# pepino4.net
KiCad netlist of a schematic drawn in EAGLE
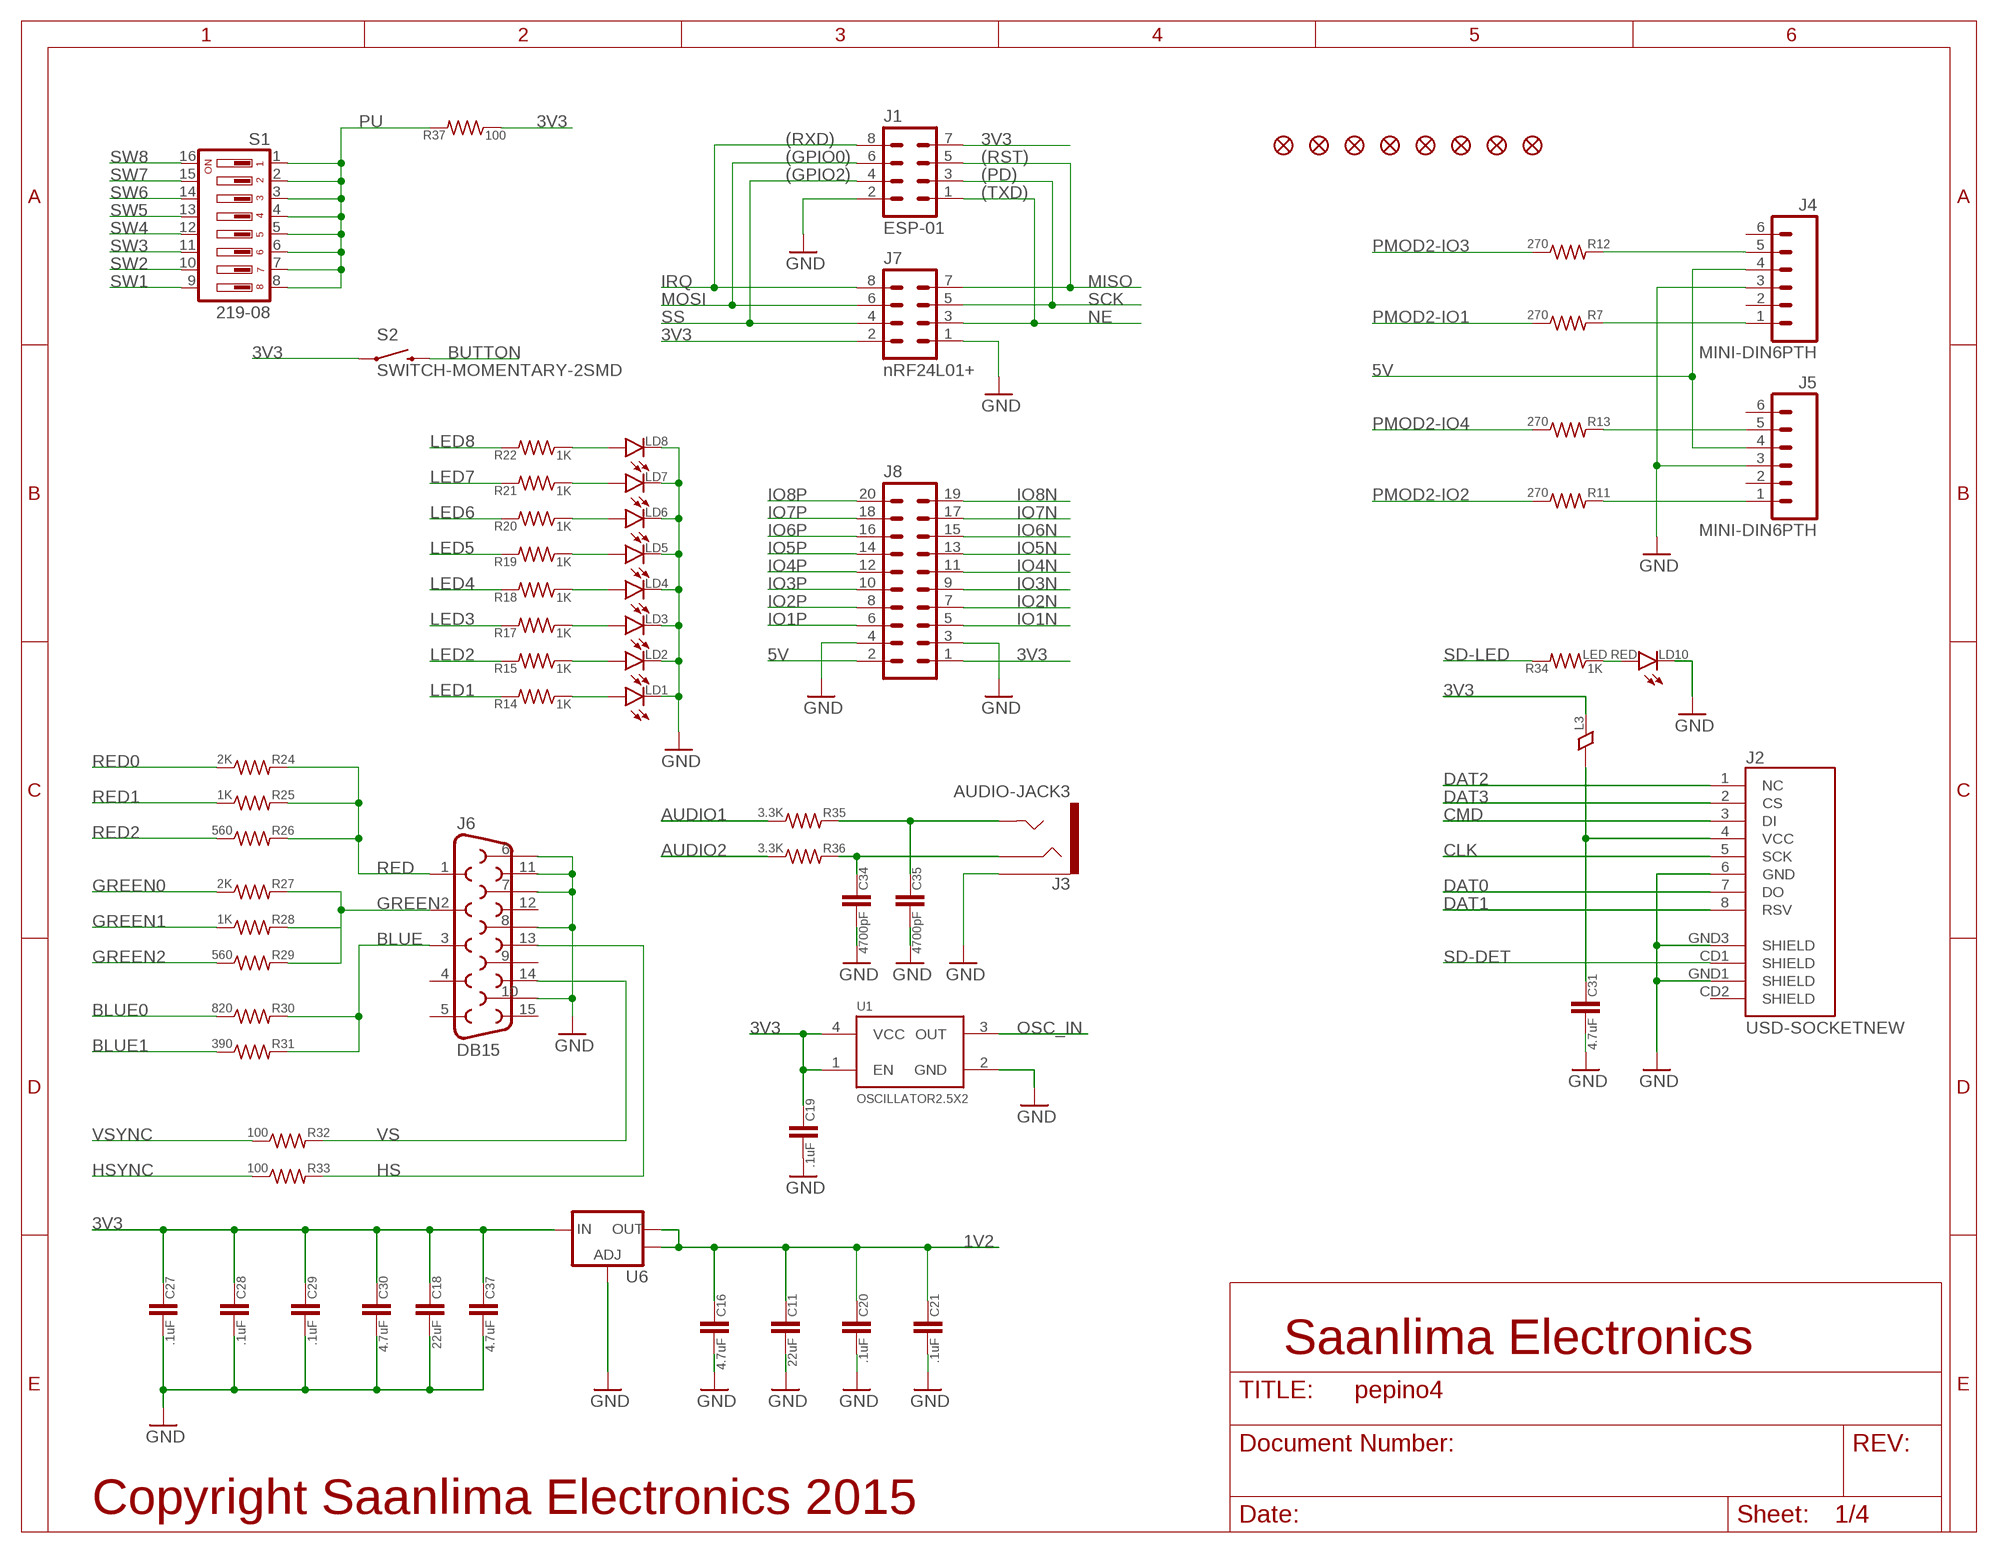
[diagram p0: schematic, sheet 1]
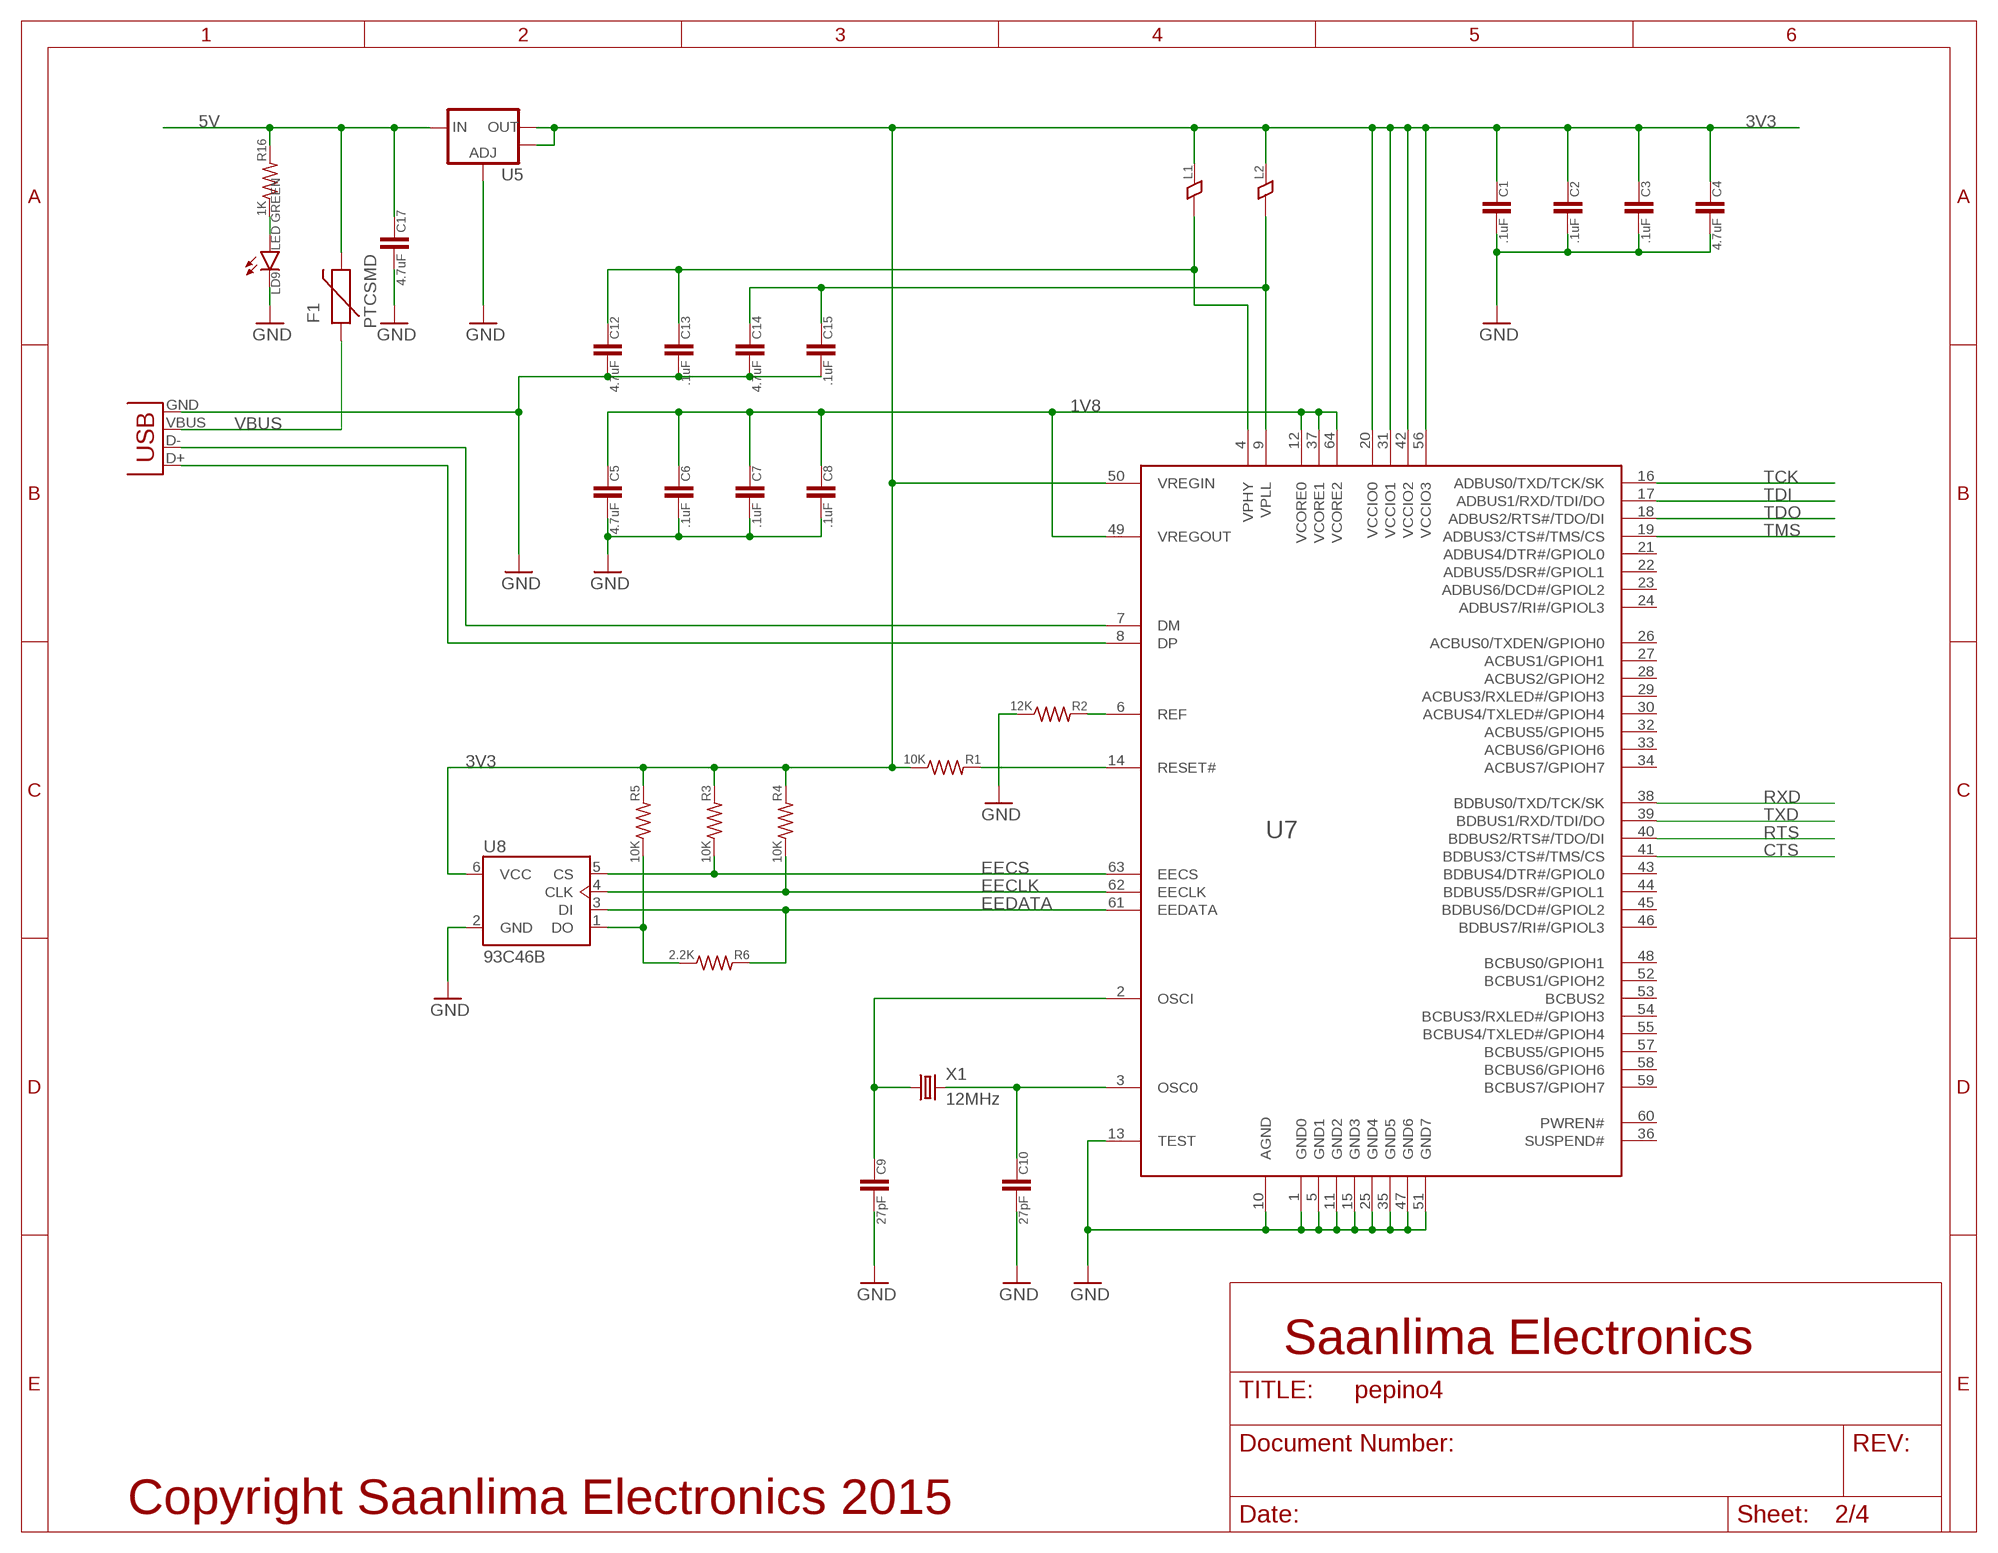
[diagram p1: schematic, sheet 2]
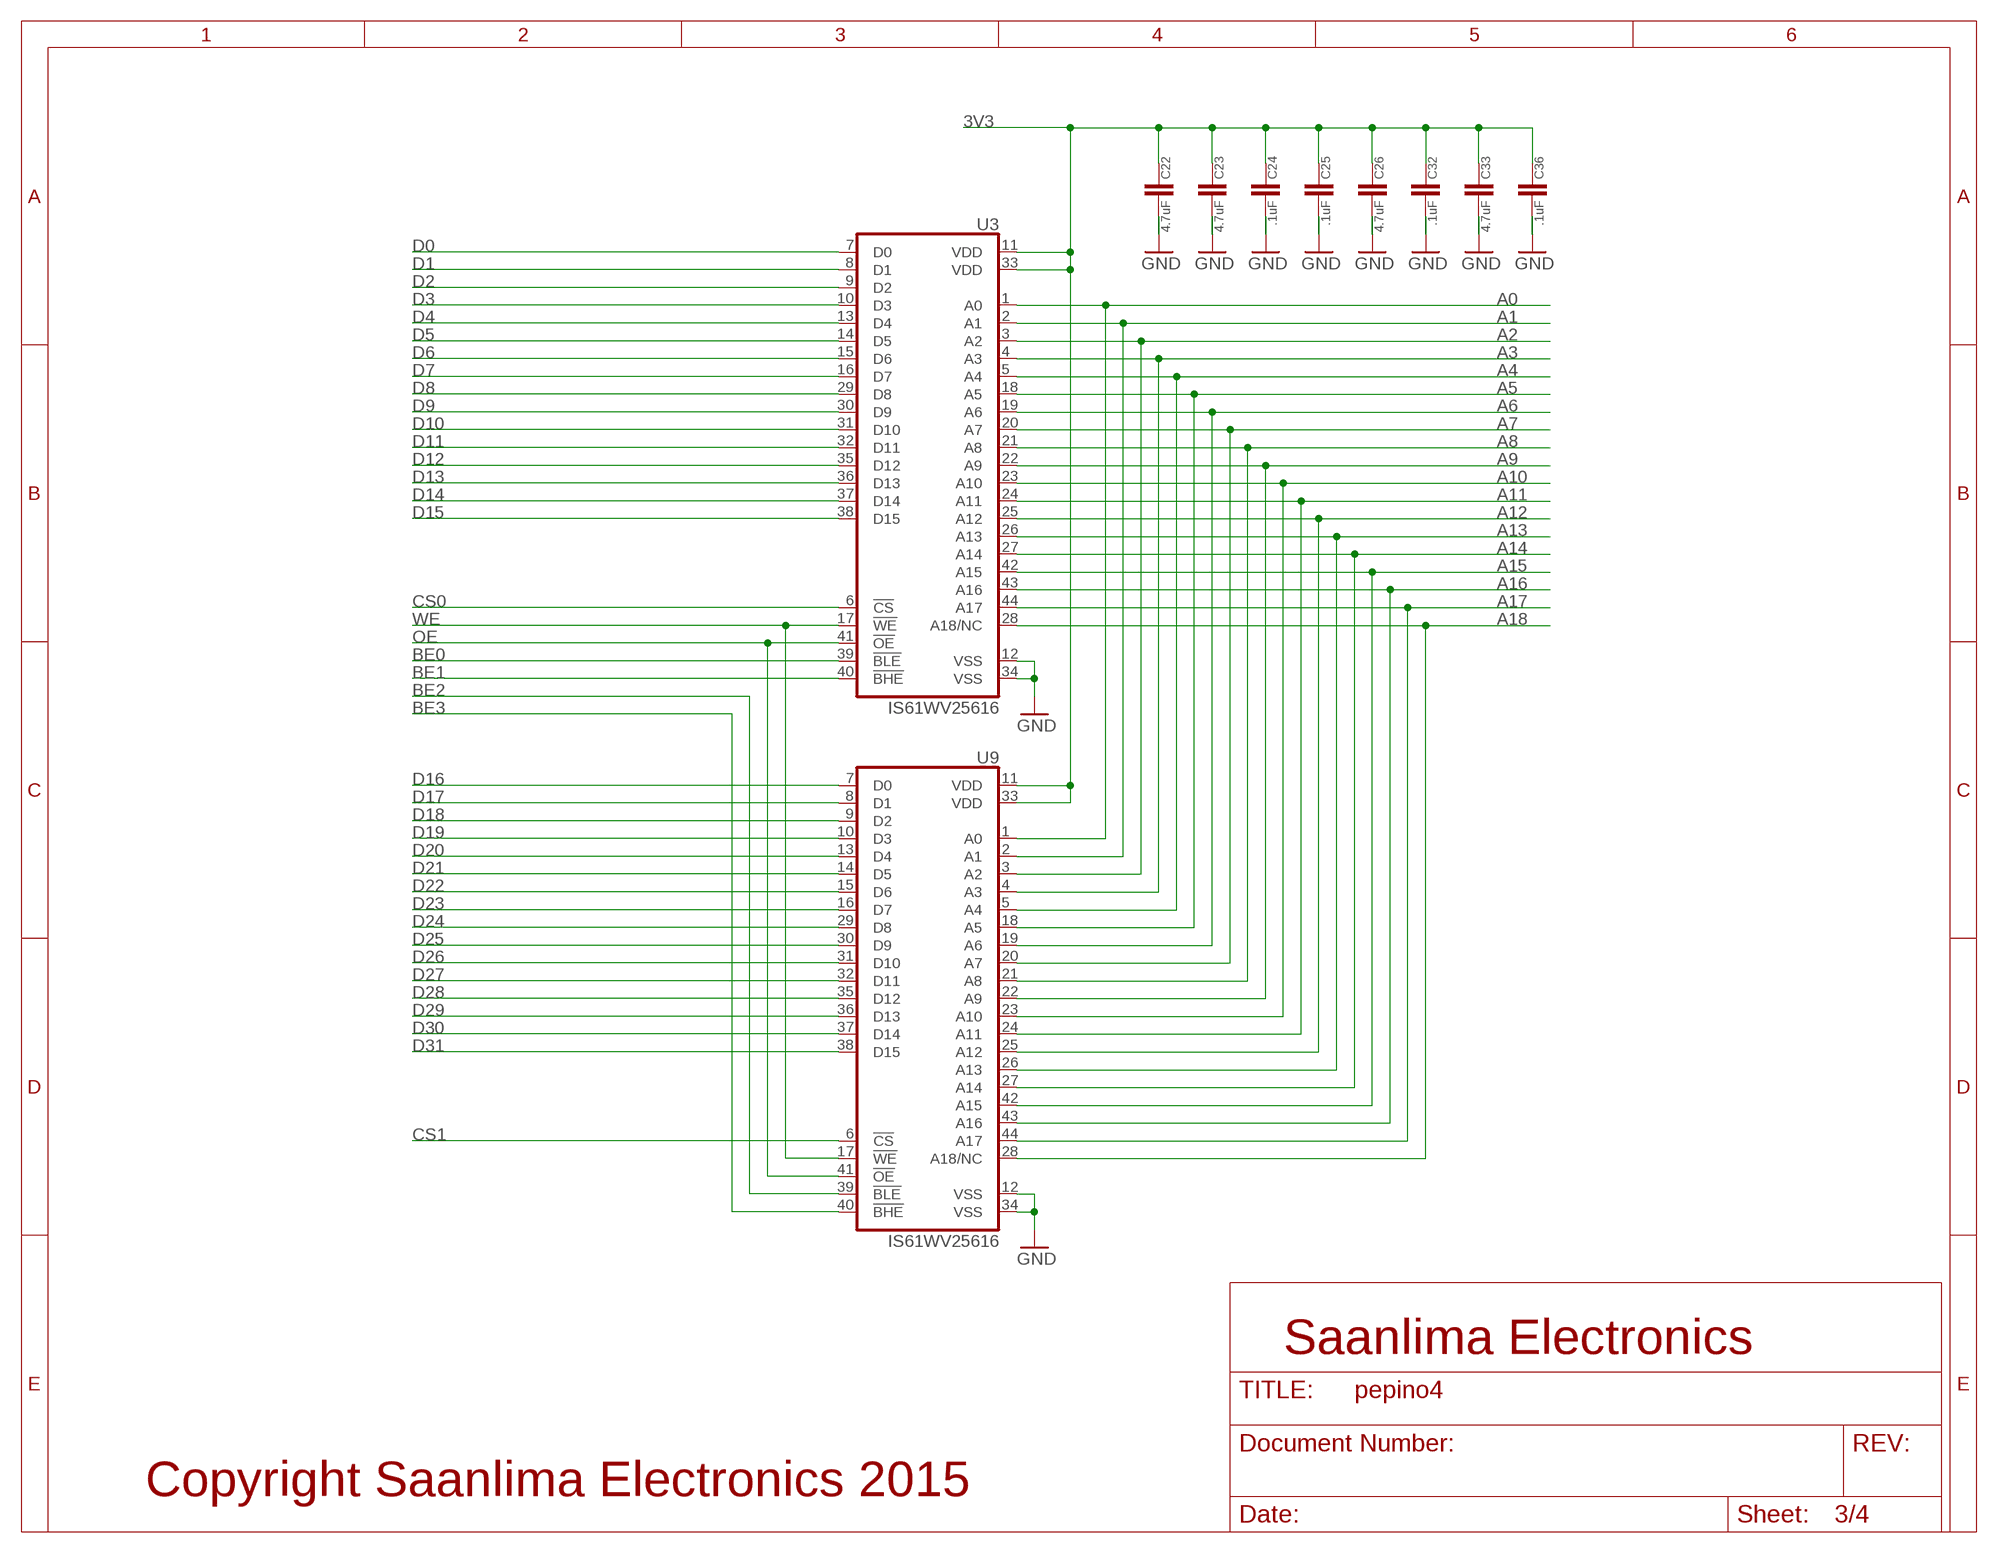
[diagram p2: schematic, sheet 3]
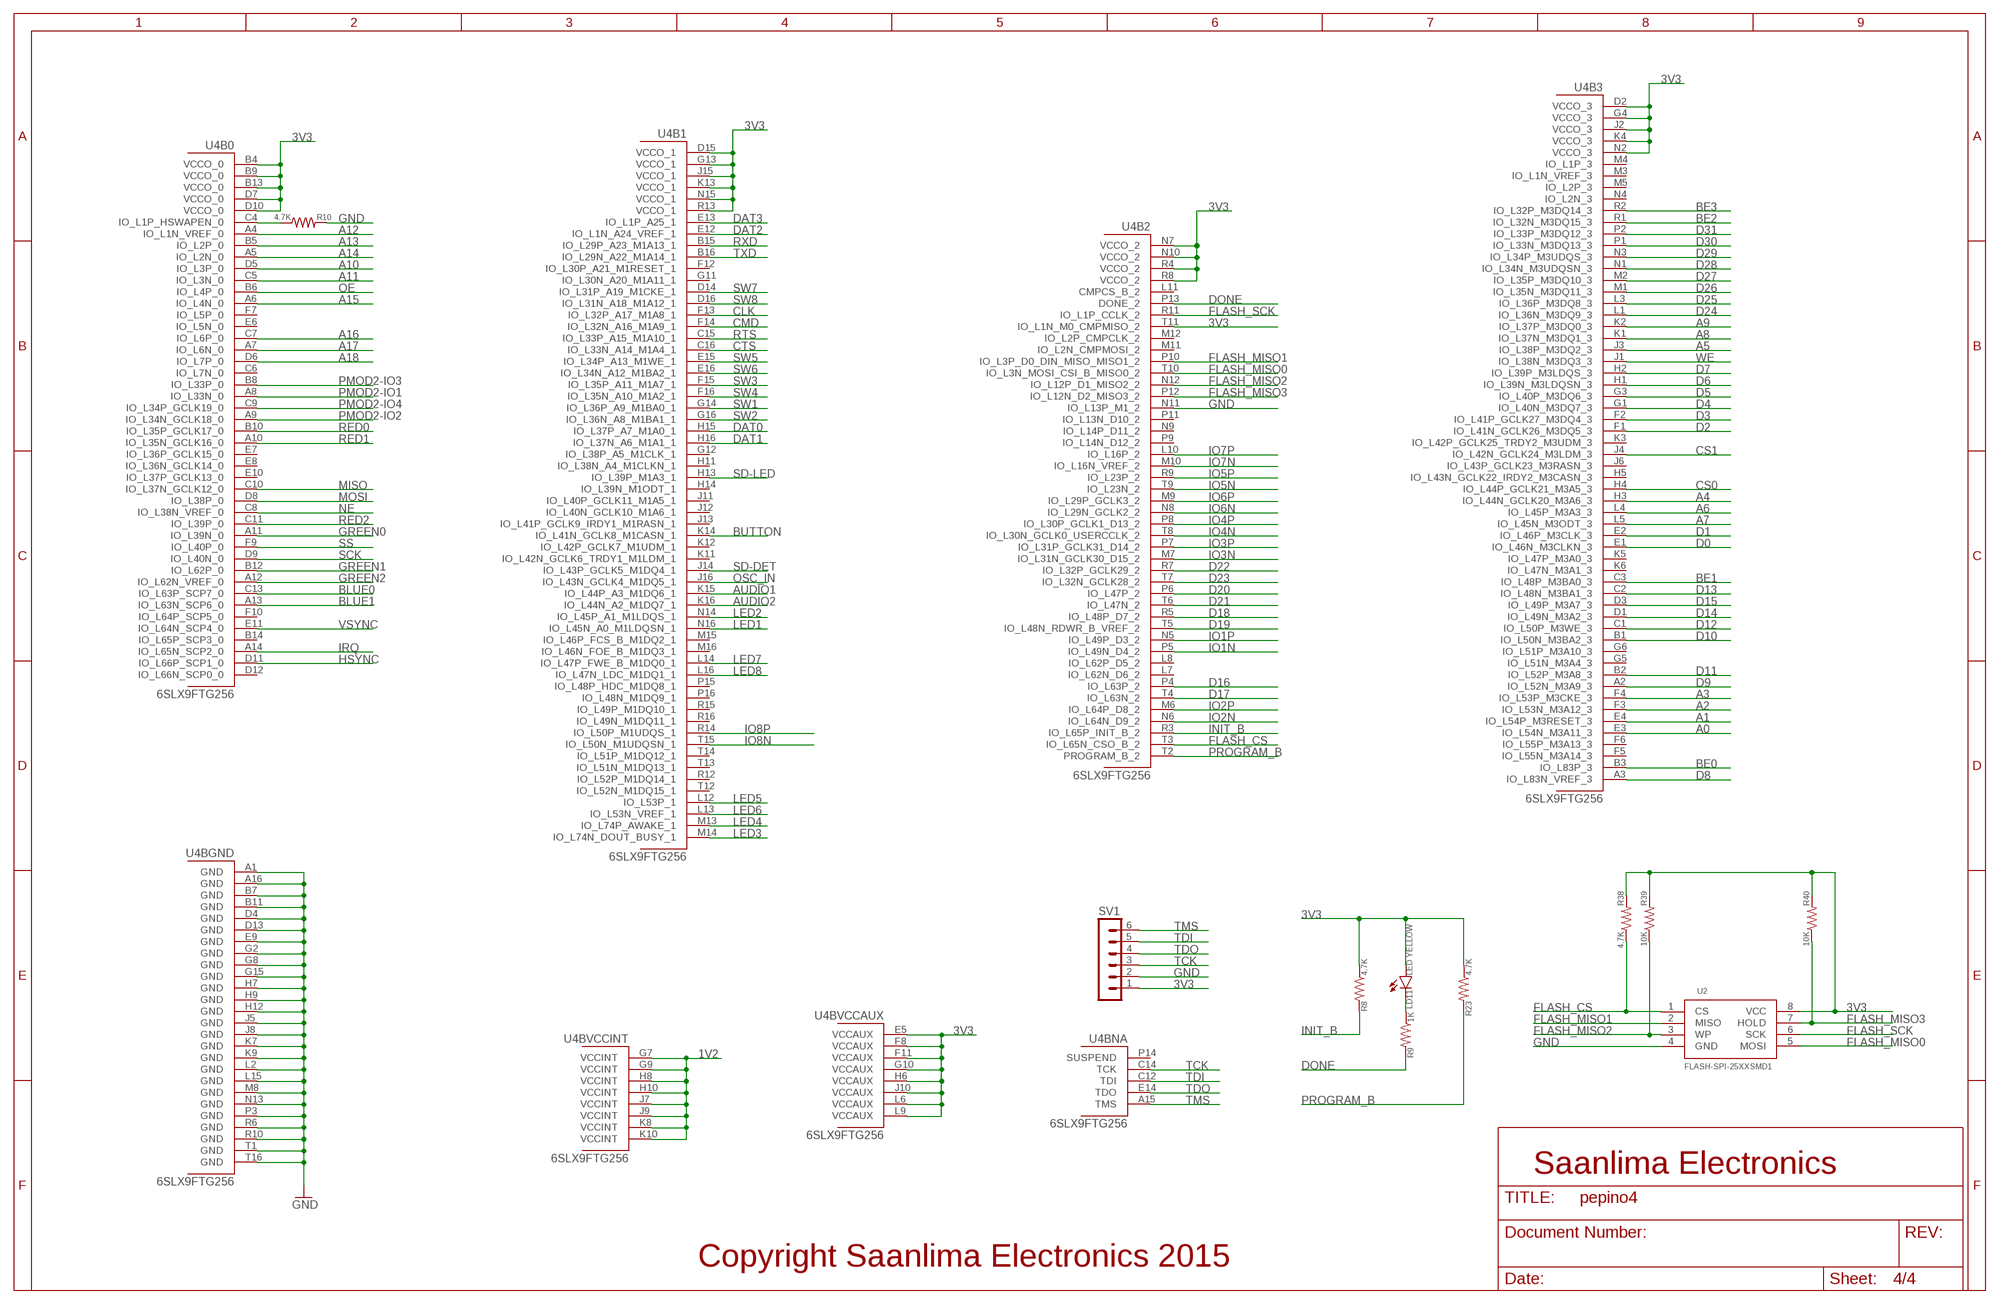
[diagram p3: schematic, sheet 4]

(export (version "E")
  (design (tool "Eeschema 10.0.6"))
  (components
    (comp (ref "C1")
      (value ".1uF")
      (footprint "eagle-import:0402")
      (libsource (lib "eagle-import") (part "saanlima_C0402"))
    )
    (comp (ref "C2")
      (value ".1uF")
      (footprint "eagle-import:0402")
      (libsource (lib "eagle-import") (part "saanlima_C0402"))
    )
    (comp (ref "C3")
      (value ".1uF")
      (footprint "eagle-import:0402")
      (libsource (lib "eagle-import") (part "saanlima_C0402"))
    )
    (comp (ref "C4")
      (value "4.7uF")
      (footprint "eagle-import:0402")
      (libsource (lib "eagle-import") (part "saanlima_C0402"))
    )
    (comp (ref "C5")
      (value "4.7uF")
      (footprint "eagle-import:0402")
      (libsource (lib "eagle-import") (part "saanlima_C0402"))
    )
    (comp (ref "C6")
      (value ".1uF")
      (footprint "eagle-import:0402")
      (libsource (lib "eagle-import") (part "saanlima_C0402"))
    )
    (comp (ref "C7")
      (value ".1uF")
      (footprint "eagle-import:0402")
      (libsource (lib "eagle-import") (part "saanlima_C0402"))
    )
    (comp (ref "C8")
      (value ".1uF")
      (footprint "eagle-import:0402")
      (libsource (lib "eagle-import") (part "saanlima_C0402"))
    )
    (comp (ref "C9")
      (value "27pF")
      (footprint "eagle-import:0402")
      (libsource (lib "eagle-import") (part "saanlima_C0402"))
    )
    (comp (ref "C10")
      (value "27pF")
      (footprint "eagle-import:0402")
      (libsource (lib "eagle-import") (part "saanlima_C0402"))
    )
    (comp (ref "C12")
      (value "4.7uF")
      (footprint "eagle-import:0402")
      (libsource (lib "eagle-import") (part "saanlima_C0402"))
    )
    (comp (ref "C13")
      (value ".1uF")
      (footprint "eagle-import:0402")
      (libsource (lib "eagle-import") (part "saanlima_C0402"))
    )
    (comp (ref "C14")
      (value "4.7uF")
      (footprint "eagle-import:0402")
      (libsource (lib "eagle-import") (part "saanlima_C0402"))
    )
    (comp (ref "C15")
      (value ".1uF")
      (footprint "eagle-import:0402")
      (libsource (lib "eagle-import") (part "saanlima_C0402"))
    )
    (comp (ref "C17")
      (value "4.7uF")
      (footprint "eagle-import:0603")
      (libsource (lib "eagle-import") (part "saanlima_C0603"))
    )
    (comp (ref "F1")
      (value "PTCSMD")
      (footprint "eagle-import:PTC-1206")
      (libsource (lib "eagle-import") (part "PTCSMD"))
    )
    (comp (ref "J9")
      (value "USBSMD")
      (footprint "eagle-import:USB-MINIB")
      (libsource (lib "eagle-import") (part "USBSMD"))
    )
    (comp (ref "L1")
      (value "FERRITE0402")
      (footprint "eagle-import:0402")
      (libsource (lib "eagle-import") (part "FERRITE0402"))
    )
    (comp (ref "L2")
      (value "FERRITE0402")
      (footprint "eagle-import:0402")
      (libsource (lib "eagle-import") (part "FERRITE0402"))
    )
    (comp (ref "LD9")
      (value "LED GREEN")
      (footprint "eagle-import:0805_POL")
      (libsource (lib "eagle-import") (part "LED0805"))
    )
    (comp (ref "R1")
      (value "10K")
      (footprint "eagle-import:0402")
      (libsource (lib "eagle-import") (part "saanlima_R0402"))
    )
    (comp (ref "R2")
      (value "12K")
      (footprint "eagle-import:0402")
      (libsource (lib "eagle-import") (part "saanlima_R0402"))
    )
    (comp (ref "R3")
      (value "10K")
      (footprint "eagle-import:0402")
      (libsource (lib "eagle-import") (part "saanlima_R0402"))
    )
    (comp (ref "R4")
      (value "10K")
      (footprint "eagle-import:0402")
      (libsource (lib "eagle-import") (part "saanlima_R0402"))
    )
    (comp (ref "R5")
      (value "10K")
      (footprint "eagle-import:0402")
      (libsource (lib "eagle-import") (part "saanlima_R0402"))
    )
    (comp (ref "R6")
      (value "2.2K")
      (footprint "eagle-import:0402")
      (libsource (lib "eagle-import") (part "saanlima_R0402"))
    )
    (comp (ref "R16")
      (value "1K")
      (footprint "eagle-import:0402")
      (libsource (lib "eagle-import") (part "saanlima_R0402"))
    )
    (comp (ref "U5")
      (value "V_REG_LM1117SOT223")
      (footprint "eagle-import:SOT223")
      (libsource (lib "eagle-import") (part "V_REG_LM1117SOT223"))
    )
    (comp (ref "U7")
      (value "DP-EAGLELIBRARY_FT2232H")
      (footprint "eagle-import:DP-EAGLELIBRARY_LQFP64")
      (libsource (lib "eagle-import") (part "DP-EAGLELIBRARY_FT2232H"))
    )
    (comp (ref "U8")
      (value "93C46B")
      (footprint "eagle-import:SOT23-6")
      (libsource (lib "eagle-import") (part "DIGITAL-EEPROM-MICROWIRE-6P_SOT23"))
    )
    (comp (ref "X1")
      (value "12MHz")
      (footprint "eagle-import:CRYSTAL3.2X2.5MM")
      (libsource (lib "eagle-import") (part "CRYSTAL3.2X2.5"))
    )
    (comp (ref "C22")
      (value "4.7uF")
      (footprint "eagle-import:0402")
      (libsource (lib "eagle-import") (part "saanlima_C0402"))
    )
    (comp (ref "C23")
      (value "4.7uF")
      (footprint "eagle-import:0402")
      (libsource (lib "eagle-import") (part "saanlima_C0402"))
    )
    (comp (ref "C24")
      (value ".1uF")
      (footprint "eagle-import:0402")
      (libsource (lib "eagle-import") (part "saanlima_C0402"))
    )
    (comp (ref "C25")
      (value ".1uF")
      (footprint "eagle-import:0402")
      (libsource (lib "eagle-import") (part "saanlima_C0402"))
    )
    (comp (ref "C26")
      (value "4.7uF")
      (footprint "eagle-import:0402")
      (libsource (lib "eagle-import") (part "saanlima_C0402"))
    )
    (comp (ref "C32")
      (value ".1uF")
      (footprint "eagle-import:0402")
      (libsource (lib "eagle-import") (part "saanlima_C0402"))
    )
    (comp (ref "C33")
      (value "4.7uF")
      (footprint "eagle-import:0402")
      (libsource (lib "eagle-import") (part "saanlima_C0402"))
    )
    (comp (ref "C36")
      (value ".1uF")
      (footprint "eagle-import:0402")
      (libsource (lib "eagle-import") (part "saanlima_C0402"))
    )
    (comp (ref "U3")
      (value "IS61WV25616")
      (footprint "eagle-import:TSOP44-II")
      (libsource (lib "eagle-import") (part "DIGITAL_4MB_SRAM"))
    )
    (comp (ref "U9")
      (value "IS61WV25616")
      (footprint "eagle-import:TSOP44-II")
      (libsource (lib "eagle-import") (part "DIGITAL_4MB_SRAM"))
    )
    (comp (ref "LD11")
      (value "LED YELLOW")
      (footprint "eagle-import:0805_POL")
      (libsource (lib "eagle-import") (part "LED0805"))
    )
    (comp (ref "R8")
      (value "4.7K")
      (footprint "eagle-import:0402")
      (libsource (lib "eagle-import") (part "saanlima_R0402"))
    )
    (comp (ref "R9")
      (value "1K")
      (footprint "eagle-import:0402")
      (libsource (lib "eagle-import") (part "saanlima_R0402"))
    )
    (comp (ref "R10")
      (value "4.7K")
      (footprint "eagle-import:0402")
      (libsource (lib "eagle-import") (part "saanlima_R0402"))
    )
    (comp (ref "R23")
      (value "4.7K")
      (footprint "eagle-import:0402")
      (libsource (lib "eagle-import") (part "saanlima_R0402"))
    )
    (comp (ref "R38")
      (value "4.7K")
      (footprint "eagle-import:0402")
      (libsource (lib "eagle-import") (part "R0402"))
    )
    (comp (ref "R39")
      (value "10K")
      (footprint "eagle-import:0402")
      (libsource (lib "eagle-import") (part "R0402"))
    )
    (comp (ref "R40")
      (value "10K")
      (footprint "eagle-import:0402")
      (libsource (lib "eagle-import") (part "R0402"))
    )
    (comp (ref "SV1")
      (value "MA06-1")
      (footprint "eagle-import:MA06-1")
      (libsource (lib "eagle-import") (part "MA06-1"))
    )
    (comp (ref "U2")
      (value "FLASH-SPI-25XXSMD1")
      (footprint "eagle-import:SO08-EIAJ")
      (libsource (lib "eagle-import") (part "FLASH-SPI-25XXSMD1"))
    )
    (comp (ref "U4")
      (value "6SLX9FTG256")
      (footprint "eagle-import:FT256")
      (libsource (lib "eagle-import") (part "6SLX9FTG256"))
    )
    (comp (ref "C11")
      (value "22uF")
      (footprint "eagle-import:0805")
      (libsource (lib "eagle-import") (part "saanlima_C0805"))
    )
    (comp (ref "C16")
      (value "4.7uF")
      (footprint "eagle-import:0402")
      (libsource (lib "eagle-import") (part "saanlima_C0402"))
    )
    (comp (ref "C18")
      (value "22uF")
      (footprint "eagle-import:0805")
      (libsource (lib "eagle-import") (part "saanlima_C0805"))
    )
    (comp (ref "C19")
      (value ".1uF")
      (footprint "eagle-import:0402")
      (libsource (lib "eagle-import") (part "saanlima_C0402"))
    )
    (comp (ref "C20")
      (value ".1uF")
      (footprint "eagle-import:0402")
      (libsource (lib "eagle-import") (part "saanlima_C0402"))
    )
    (comp (ref "C21")
      (value ".1uF")
      (footprint "eagle-import:0402")
      (libsource (lib "eagle-import") (part "saanlima_C0402"))
    )
    (comp (ref "C27")
      (value ".1uF")
      (footprint "eagle-import:0402")
      (libsource (lib "eagle-import") (part "saanlima_C0402"))
    )
    (comp (ref "C28")
      (value ".1uF")
      (footprint "eagle-import:0402")
      (libsource (lib "eagle-import") (part "saanlima_C0402"))
    )
    (comp (ref "C29")
      (value ".1uF")
      (footprint "eagle-import:0402")
      (libsource (lib "eagle-import") (part "saanlima_C0402"))
    )
    (comp (ref "C30")
      (value "4.7uF")
      (footprint "eagle-import:0402")
      (libsource (lib "eagle-import") (part "saanlima_C0402"))
    )
    (comp (ref "C31")
      (value "4.7uF")
      (footprint "eagle-import:0402")
      (libsource (lib "eagle-import") (part "saanlima_C0402"))
    )
    (comp (ref "C34")
      (value "4700pF")
      (footprint "eagle-import:0402")
      (libsource (lib "eagle-import") (part "C0402"))
    )
    (comp (ref "C35")
      (value "4700pF")
      (footprint "eagle-import:0402")
      (libsource (lib "eagle-import") (part "C0402"))
    )
    (comp (ref "C37")
      (value "4.7uF")
      (footprint "eagle-import:0402")
      (libsource (lib "eagle-import") (part "saanlima_C0402"))
    )
    (comp (ref "J1")
      (value "ESP-01")
      (footprint "eagle-import:MA04-2")
      (libsource (lib "eagle-import") (part "MA04-2"))
    )
    (comp (ref "J2")
      (value "USD-SOCKETNEW")
      (footprint "eagle-import:MICRO-SD-SOCKET-PP")
      (libsource (lib "eagle-import") (part "USD-SOCKETNEW"))
    )
    (comp (ref "J3")
      (value "AUDIO-JACK3")
      (footprint "eagle-import:AUDIO-JACK-3.5MM-3")
      (libsource (lib "eagle-import") (part "AUDIO-JACK3"))
    )
    (comp (ref "J4")
      (value "MINI-DIN6PTH")
      (footprint "eagle-import:MINI-DIN6")
      (libsource (lib "eagle-import") (part "MINI-DIN6PTH"))
    )
    (comp (ref "J5")
      (value "MINI-DIN6PTH")
      (footprint "eagle-import:MINI-DIN6")
      (libsource (lib "eagle-import") (part "MINI-DIN6PTH"))
    )
    (comp (ref "J6")
      (value "DB15")
      (footprint "eagle-import:DB15")
      (libsource (lib "eagle-import") (part "DB15"))
    )
    (comp (ref "J7")
      (value "nRF24L01+")
      (footprint "eagle-import:MA04-2")
      (libsource (lib "eagle-import") (part "MA04-2"))
    )
    (comp (ref "J8")
      (value "MA10-2")
      (footprint "eagle-import:MA10-2")
      (libsource (lib "eagle-import") (part "MA10-2"))
    )
    (comp (ref "JP1")
      (value "FIDUCIAL1X2")
      (footprint "eagle-import:FIDUCIAL-1X2")
      (libsource (lib "eagle-import") (part "FIDUCIAL1X2"))
    )
    (comp (ref "JP2")
      (value "FIDUCIAL1X2")
      (footprint "eagle-import:FIDUCIAL-1X2")
      (libsource (lib "eagle-import") (part "FIDUCIAL1X2"))
    )
    (comp (ref "JP3")
      (value "FIDUCIAL1X2")
      (footprint "eagle-import:FIDUCIAL-1X2")
      (libsource (lib "eagle-import") (part "FIDUCIAL1X2"))
    )
    (comp (ref "JP4")
      (value "FIDUCIAL1X2")
      (footprint "eagle-import:FIDUCIAL-1X2")
      (libsource (lib "eagle-import") (part "FIDUCIAL1X2"))
    )
    (comp (ref "JP5")
      (value "FIDUCIAL1X2")
      (footprint "eagle-import:FIDUCIAL-1X2")
      (libsource (lib "eagle-import") (part "FIDUCIAL1X2"))
    )
    (comp (ref "JP6")
      (value "FIDUCIAL1X2")
      (footprint "eagle-import:FIDUCIAL-1X2")
      (libsource (lib "eagle-import") (part "FIDUCIAL1X2"))
    )
    (comp (ref "JP7")
      (value "FIDUCIAL1X2")
      (footprint "eagle-import:FIDUCIAL-1X2")
      (libsource (lib "eagle-import") (part "FIDUCIAL1X2"))
    )
    (comp (ref "JP8")
      (value "FIDUCIAL1X2")
      (footprint "eagle-import:FIDUCIAL-1X2")
      (libsource (lib "eagle-import") (part "FIDUCIAL1X2"))
    )
    (comp (ref "L3")
      (value "FERRITE0402")
      (footprint "eagle-import:0402")
      (libsource (lib "eagle-import") (part "FERRITE0402"))
    )
    (comp (ref "LD1")
      (value "LED0805")
      (footprint "eagle-import:0805_POL")
      (libsource (lib "eagle-import") (part "LED0805"))
    )
    (comp (ref "LD2")
      (value "LED0805")
      (footprint "eagle-import:0805_POL")
      (libsource (lib "eagle-import") (part "LED0805"))
    )
    (comp (ref "LD3")
      (value "LED0805")
      (footprint "eagle-import:0805_POL")
      (libsource (lib "eagle-import") (part "LED0805"))
    )
    (comp (ref "LD4")
      (value "LED0805")
      (footprint "eagle-import:0805_POL")
      (libsource (lib "eagle-import") (part "LED0805"))
    )
    (comp (ref "LD5")
      (value "LED0805")
      (footprint "eagle-import:0805_POL")
      (libsource (lib "eagle-import") (part "LED0805"))
    )
    (comp (ref "LD6")
      (value "LED0805")
      (footprint "eagle-import:0805_POL")
      (libsource (lib "eagle-import") (part "LED0805"))
    )
    (comp (ref "LD7")
      (value "LED0805")
      (footprint "eagle-import:0805_POL")
      (libsource (lib "eagle-import") (part "LED0805"))
    )
    (comp (ref "LD8")
      (value "LED0805")
      (footprint "eagle-import:0805_POL")
      (libsource (lib "eagle-import") (part "LED0805"))
    )
    (comp (ref "LD10")
      (value "LED RED")
      (footprint "eagle-import:0805_POL")
      (libsource (lib "eagle-import") (part "LED0805"))
    )
    (comp (ref "R7")
      (value "270")
      (footprint "eagle-import:0402")
      (libsource (lib "eagle-import") (part "saanlima_R0402"))
    )
    (comp (ref "R11")
      (value "270")
      (footprint "eagle-import:0402")
      (libsource (lib "eagle-import") (part "saanlima_R0402"))
    )
    (comp (ref "R12")
      (value "270")
      (footprint "eagle-import:0402")
      (libsource (lib "eagle-import") (part "saanlima_R0402"))
    )
    (comp (ref "R13")
      (value "270")
      (footprint "eagle-import:0402")
      (libsource (lib "eagle-import") (part "saanlima_R0402"))
    )
    (comp (ref "R14")
      (value "1K")
      (footprint "eagle-import:0402")
      (libsource (lib "eagle-import") (part "saanlima_R0402"))
    )
    (comp (ref "R15")
      (value "1K")
      (footprint "eagle-import:0402")
      (libsource (lib "eagle-import") (part "saanlima_R0402"))
    )
    (comp (ref "R17")
      (value "1K")
      (footprint "eagle-import:0402")
      (libsource (lib "eagle-import") (part "saanlima_R0402"))
    )
    (comp (ref "R18")
      (value "1K")
      (footprint "eagle-import:0402")
      (libsource (lib "eagle-import") (part "saanlima_R0402"))
    )
    (comp (ref "R19")
      (value "1K")
      (footprint "eagle-import:0402")
      (libsource (lib "eagle-import") (part "saanlima_R0402"))
    )
    (comp (ref "R20")
      (value "1K")
      (footprint "eagle-import:0402")
      (libsource (lib "eagle-import") (part "saanlima_R0402"))
    )
    (comp (ref "R21")
      (value "1K")
      (footprint "eagle-import:0402")
      (libsource (lib "eagle-import") (part "saanlima_R0402"))
    )
    (comp (ref "R22")
      (value "1K")
      (footprint "eagle-import:0402")
      (libsource (lib "eagle-import") (part "saanlima_R0402"))
    )
    (comp (ref "R24")
      (value "2K")
      (footprint "eagle-import:0402")
      (libsource (lib "eagle-import") (part "saanlima_R0402"))
    )
    (comp (ref "R25")
      (value "1K")
      (footprint "eagle-import:0402")
      (libsource (lib "eagle-import") (part "saanlima_R0402"))
    )
    (comp (ref "R26")
      (value "560")
      (footprint "eagle-import:0402")
      (libsource (lib "eagle-import") (part "saanlima_R0402"))
    )
    (comp (ref "R27")
      (value "2K")
      (footprint "eagle-import:0402")
      (libsource (lib "eagle-import") (part "saanlima_R0402"))
    )
    (comp (ref "R28")
      (value "1K")
      (footprint "eagle-import:0402")
      (libsource (lib "eagle-import") (part "saanlima_R0402"))
    )
    (comp (ref "R29")
      (value "560")
      (footprint "eagle-import:0402")
      (libsource (lib "eagle-import") (part "saanlima_R0402"))
    )
    (comp (ref "R30")
      (value "820")
      (footprint "eagle-import:0402")
      (libsource (lib "eagle-import") (part "saanlima_R0402"))
    )
    (comp (ref "R31")
      (value "390")
      (footprint "eagle-import:0402")
      (libsource (lib "eagle-import") (part "saanlima_R0402"))
    )
    (comp (ref "R32")
      (value "100")
      (footprint "eagle-import:0402")
      (libsource (lib "eagle-import") (part "saanlima_R0402"))
    )
    (comp (ref "R33")
      (value "100")
      (footprint "eagle-import:0402")
      (libsource (lib "eagle-import") (part "saanlima_R0402"))
    )
    (comp (ref "R34")
      (value "1K")
      (footprint "eagle-import:0402")
      (libsource (lib "eagle-import") (part "saanlima_R0402"))
    )
    (comp (ref "R35")
      (value "3.3K")
      (footprint "eagle-import:0402")
      (libsource (lib "eagle-import") (part "R0402"))
    )
    (comp (ref "R36")
      (value "3.3K")
      (footprint "eagle-import:0402")
      (libsource (lib "eagle-import") (part "R0402"))
    )
    (comp (ref "R37")
      (value "100")
      (footprint "eagle-import:0402")
      (libsource (lib "eagle-import") (part "saanlima_R0402"))
    )
    (comp (ref "S1")
      (value "219-08")
      (footprint "eagle-import:CTS-219-08")
      (fields (field (name "OC_FARNELL") "unknown") (field (name "OC_NEWARK") "unknown"))
      (libsource (lib "eagle-import") (part "219-08"))
    )
    (comp (ref "S2")
      (value "SWITCH-MOMENTARY-2SMD")
      (footprint "eagle-import:TACTILE_SWITCH_SMD")
      (libsource (lib "eagle-import") (part "SWITCH-MOMENTARY-2SMD"))
    )
    (comp (ref "U1")
      (value "OSCILLATOR2.5X2")
      (footprint "eagle-import:CRYSTAL-OSC-SMD-2.5X2")
      (libsource (lib "eagle-import") (part "OSCILLATOR2.5X2"))
    )
    (comp (ref "U6")
      (value "V_REG_LM1117SOT223")
      (footprint "eagle-import:SOT223")
      (libsource (lib "eagle-import") (part "V_REG_LM1117SOT223"))
    )
  )
  (nets
    (net (code "1") (name "1V2") (class "Default")
      (node (ref "C11") (pin "1") (pinfunction "1_1") (pintype "passive"))
      (node (ref "C16") (pin "1") (pinfunction "1_1") (pintype "passive"))
      (node (ref "C20") (pin "1") (pinfunction "1_1") (pintype "passive"))
      (node (ref "C21") (pin "1") (pinfunction "1_1") (pintype "passive"))
      (node (ref "U4") (pin "G7") (pinfunction "VCCINT_G7") (pintype "input"))
      (node (ref "U4") (pin "G9") (pinfunction "VCCINT_G9") (pintype "input"))
      (node (ref "U4") (pin "H10") (pinfunction "VCCINT_H10") (pintype "input"))
      (node (ref "U4") (pin "H8") (pinfunction "VCCINT_H8") (pintype "input"))
      (node (ref "U4") (pin "J7") (pinfunction "VCCINT_J7") (pintype "input"))
      (node (ref "U4") (pin "J9") (pinfunction "VCCINT_J9") (pintype "input"))
      (node (ref "U4") (pin "K10") (pinfunction "VCCINT_K10") (pintype "input"))
      (node (ref "U4") (pin "K8") (pinfunction "VCCINT_K8") (pintype "input"))
      (node (ref "U6") (pin "2") (pinfunction "OUT_2") (pintype "output"))
      (node (ref "U6") (pin "4") (pinfunction "OUT_4") (pintype "output"))
    )
    (net (code "2") (name "1V8") (class "Default")
      (node (ref "C5") (pin "1") (pinfunction "1_1") (pintype "passive"))
      (node (ref "C6") (pin "1") (pinfunction "1_1") (pintype "passive"))
      (node (ref "C7") (pin "1") (pinfunction "1_1") (pintype "passive"))
      (node (ref "C8") (pin "1") (pinfunction "1_1") (pintype "passive"))
      (node (ref "U7") (pin "12") (pinfunction "VCORE0_12") (pintype "bidirectional"))
      (node (ref "U7") (pin "37") (pinfunction "VCORE1_37") (pintype "bidirectional"))
      (node (ref "U7") (pin "49") (pinfunction "VREGOUT_49") (pintype "bidirectional"))
      (node (ref "U7") (pin "64") (pinfunction "VCORE2_64") (pintype "bidirectional"))
    )
    (net (code "3") (name "3V3") (class "Default")
      (node (ref "C1") (pin "1") (pinfunction "1_1") (pintype "passive"))
      (node (ref "C18") (pin "1") (pinfunction "1_1") (pintype "passive"))
      (node (ref "C19") (pin "1") (pinfunction "1_1") (pintype "passive"))
      (node (ref "C2") (pin "1") (pinfunction "1_1") (pintype "passive"))
      (node (ref "C22") (pin "1") (pinfunction "1_1") (pintype "passive"))
      (node (ref "C23") (pin "1") (pinfunction "1_1") (pintype "passive"))
      (node (ref "C24") (pin "1") (pinfunction "1_1") (pintype "passive"))
      (node (ref "C25") (pin "1") (pinfunction "1_1") (pintype "passive"))
      (node (ref "C26") (pin "1") (pinfunction "1_1") (pintype "passive"))
      (node (ref "C27") (pin "1") (pinfunction "1_1") (pintype "passive"))
      (node (ref "C28") (pin "1") (pinfunction "1_1") (pintype "passive"))
      (node (ref "C29") (pin "1") (pinfunction "1_1") (pintype "passive"))
      (node (ref "C3") (pin "1") (pinfunction "1_1") (pintype "passive"))
      (node (ref "C30") (pin "1") (pinfunction "1_1") (pintype "passive"))
      (node (ref "C32") (pin "1") (pinfunction "1_1") (pintype "passive"))
      (node (ref "C33") (pin "1") (pinfunction "1_1") (pintype "passive"))
      (node (ref "C36") (pin "1") (pinfunction "1_1") (pintype "passive"))
      (node (ref "C37") (pin "1") (pinfunction "1_1") (pintype "passive"))
      (node (ref "C4") (pin "1") (pinfunction "1_1") (pintype "passive"))
      (node (ref "J1") (pin "7") (pinfunction "7_7") (pintype "passive"))
      (node (ref "J7") (pin "2") (pinfunction "2_2") (pintype "passive"))
      (node (ref "J8") (pin "1") (pinfunction "1_1") (pintype "passive"))
      (node (ref "L1") (pin "2") (pinfunction "2_2") (pintype "passive"))
      (node (ref "L2") (pin "2") (pinfunction "2_2") (pintype "passive"))
      (node (ref "L3") (pin "2") (pinfunction "2_2") (pintype "passive"))
      (node (ref "LD11") (pin "+") (pinfunction "A_+") (pintype "passive"))
      (node (ref "R1") (pin "1") (pinfunction "1_1") (pintype "passive"))
      (node (ref "R23") (pin "1") (pinfunction "1_1") (pintype "passive"))
      (node (ref "R3") (pin "2") (pinfunction "2_2") (pintype "passive"))
      (node (ref "R37") (pin "1") (pinfunction "1_1") (pintype "passive"))
      (node (ref "R38") (pin "2") (pinfunction "2_2") (pintype "passive"))
      (node (ref "R39") (pin "2") (pinfunction "2_2") (pintype "passive"))
      (node (ref "R4") (pin "2") (pinfunction "2_2") (pintype "passive"))
      (node (ref "R40") (pin "2") (pinfunction "2_2") (pintype "passive"))
      (node (ref "R5") (pin "2") (pinfunction "2_2") (pintype "passive"))
      (node (ref "R8") (pin "1") (pinfunction "1_1") (pintype "passive"))
      (node (ref "S2") (pin "1") (pinfunction "1_1") (pintype "passive"))
      (node (ref "SV1") (pin "1") (pinfunction "1_1") (pintype "passive"))
      (node (ref "U1") (pin "1") (pinfunction "EN_1") (pintype "bidirectional"))
      (node (ref "U1") (pin "4") (pinfunction "VCC_4") (pintype "bidirectional"))
      (node (ref "U2") (pin "8") (pinfunction "VCC_8") (pintype "bidirectional"))
      (node (ref "U3") (pin "11") (pinfunction "VDD_11") (pintype "input"))
      (node (ref "U3") (pin "33") (pinfunction "VDD_33") (pintype "input"))
      (node (ref "U4") (pin "B13") (pinfunction "VCCO_0_B13") (pintype "input"))
      (node (ref "U4") (pin "B4") (pinfunction "VCCO_0_B4") (pintype "input"))
      (node (ref "U4") (pin "B9") (pinfunction "VCCO_0_B9") (pintype "input"))
      (node (ref "U4") (pin "D10") (pinfunction "VCCO_0_D10") (pintype "input"))
      (node (ref "U4") (pin "D15") (pinfunction "VCCO_1_D15") (pintype "input"))
      (node (ref "U4") (pin "D2") (pinfunction "VCCO_3_D2") (pintype "input"))
      (node (ref "U4") (pin "D7") (pinfunction "VCCO_0_D7") (pintype "input"))
      (node (ref "U4") (pin "E5") (pinfunction "VCCAUX_E5") (pintype "input"))
      (node (ref "U4") (pin "F11") (pinfunction "VCCAUX_F11") (pintype "input"))
      (node (ref "U4") (pin "F8") (pinfunction "VCCAUX_F8") (pintype "input"))
      (node (ref "U4") (pin "G10") (pinfunction "VCCAUX_G10") (pintype "input"))
      (node (ref "U4") (pin "G13") (pinfunction "VCCO_1_G13") (pintype "input"))
      (node (ref "U4") (pin "G4") (pinfunction "VCCO_3_G4") (pintype "input"))
      (node (ref "U4") (pin "H6") (pinfunction "VCCAUX_H6") (pintype "input"))
      (node (ref "U4") (pin "J10") (pinfunction "VCCAUX_J10") (pintype "input"))
      (node (ref "U4") (pin "J15") (pinfunction "VCCO_1_J15") (pintype "input"))
      (node (ref "U4") (pin "J2") (pinfunction "VCCO_3_J2") (pintype "input"))
      (node (ref "U4") (pin "K13") (pinfunction "VCCO_1_K13") (pintype "input"))
      (node (ref "U4") (pin "K4") (pinfunction "VCCO_3_K4") (pintype "input"))
      (node (ref "U4") (pin "L6") (pinfunction "VCCAUX_L6") (pintype "input"))
      (node (ref "U4") (pin "L9") (pinfunction "VCCAUX_L9") (pintype "input"))
      (node (ref "U4") (pin "N10") (pinfunction "VCCO_2_N10") (pintype "input"))
      (node (ref "U4") (pin "N15") (pinfunction "VCCO_1_N15") (pintype "input"))
      (node (ref "U4") (pin "N2") (pinfunction "VCCO_3_N2") (pintype "input"))
      (node (ref "U4") (pin "N7") (pinfunction "VCCO_2_N7") (pintype "input"))
      (node (ref "U4") (pin "R13") (pinfunction "VCCO_1_R13") (pintype "input"))
      (node (ref "U4") (pin "R4") (pinfunction "VCCO_2_R4") (pintype "input"))
      (node (ref "U4") (pin "R8") (pinfunction "VCCO_2_R8") (pintype "input"))
      (node (ref "U4") (pin "T11") (pinfunction "IO_L1N_M0_CMPMISO_2_T11") (pintype "bidirectional"))
      (node (ref "U5") (pin "2") (pinfunction "OUT_2") (pintype "output"))
      (node (ref "U5") (pin "4") (pinfunction "OUT_4") (pintype "output"))
      (node (ref "U6") (pin "3") (pinfunction "IN_3") (pintype "input"))
      (node (ref "U7") (pin "20") (pinfunction "VCCIO0_20") (pintype "bidirectional"))
      (node (ref "U7") (pin "31") (pinfunction "VCCIO1_31") (pintype "bidirectional"))
      (node (ref "U7") (pin "42") (pinfunction "VCCIO2_42") (pintype "bidirectional"))
      (node (ref "U7") (pin "50") (pinfunction "VREGIN_50") (pintype "bidirectional"))
      (node (ref "U7") (pin "56") (pinfunction "VCCIO3_56") (pintype "bidirectional"))
      (node (ref "U8") (pin "6") (pinfunction "VCC_6") (pintype "input"))
      (node (ref "U9") (pin "11") (pinfunction "VDD_11") (pintype "input"))
      (node (ref "U9") (pin "33") (pinfunction "VDD_33") (pintype "input"))
    )
    (net (code "4") (name "5V") (class "Default")
      (node (ref "C17") (pin "1") (pinfunction "1_1") (pintype "passive"))
      (node (ref "F1") (pin "2") (pinfunction "2_2") (pintype "bidirectional"))
      (node (ref "J4") (pin "4") (pinfunction "4_4") (pintype "passive"))
      (node (ref "J5") (pin "4") (pinfunction "4_4") (pintype "passive"))
      (node (ref "J8") (pin "2") (pinfunction "2_2") (pintype "passive"))
      (node (ref "R16") (pin "2") (pinfunction "2_2") (pintype "passive"))
      (node (ref "U5") (pin "3") (pinfunction "IN_3") (pintype "input"))
    )
    (net (code "5") (name "A0") (class "Default")
      (node (ref "U3") (pin "1") (pinfunction "A0_1") (pintype "input"))
      (node (ref "U4") (pin "E3") (pinfunction "IO_L54N_M3A11_3_E3") (pintype "bidirectional"))
      (node (ref "U9") (pin "1") (pinfunction "A0_1") (pintype "input"))
    )
    (net (code "6") (name "A1") (class "Default")
      (node (ref "U3") (pin "2") (pinfunction "A1_2") (pintype "input"))
      (node (ref "U4") (pin "E4") (pinfunction "IO_L54P_M3RESET_3_E4") (pintype "bidirectional"))
      (node (ref "U9") (pin "2") (pinfunction "A1_2") (pintype "input"))
    )
    (net (code "7") (name "A2") (class "Default")
      (node (ref "U3") (pin "3") (pinfunction "A2_3") (pintype "input"))
      (node (ref "U4") (pin "F3") (pinfunction "IO_L53N_M3A12_3_F3") (pintype "bidirectional"))
      (node (ref "U9") (pin "3") (pinfunction "A2_3") (pintype "input"))
    )
    (net (code "8") (name "A3") (class "Default")
      (node (ref "U3") (pin "4") (pinfunction "A3_4") (pintype "input"))
      (node (ref "U4") (pin "F4") (pinfunction "IO_L53P_M3CKE_3_F4") (pintype "bidirectional"))
      (node (ref "U9") (pin "4") (pinfunction "A3_4") (pintype "input"))
    )
    (net (code "9") (name "A4") (class "Default")
      (node (ref "U3") (pin "5") (pinfunction "A4_5") (pintype "input"))
      (node (ref "U4") (pin "H3") (pinfunction "IO_L44N_GCLK20_M3A6_3_H3") (pintype "bidirectional"))
      (node (ref "U9") (pin "5") (pinfunction "A4_5") (pintype "input"))
    )
    (net (code "10") (name "A5") (class "Default")
      (node (ref "U3") (pin "18") (pinfunction "A5_18") (pintype "input"))
      (node (ref "U4") (pin "J3") (pinfunction "IO_L38P_M3DQ2_3_J3") (pintype "bidirectional"))
      (node (ref "U9") (pin "18") (pinfunction "A5_18") (pintype "input"))
    )
    (net (code "11") (name "A6") (class "Default")
      (node (ref "U3") (pin "19") (pinfunction "A6_19") (pintype "input"))
      (node (ref "U4") (pin "L4") (pinfunction "IO_L45P_M3A3_3_L4") (pintype "bidirectional"))
      (node (ref "U9") (pin "19") (pinfunction "A6_19") (pintype "input"))
    )
    (net (code "12") (name "A7") (class "Default")
      (node (ref "U3") (pin "20") (pinfunction "A7_20") (pintype "input"))
      (node (ref "U4") (pin "L5") (pinfunction "IO_L45N_M3ODT_3_L5") (pintype "bidirectional"))
      (node (ref "U9") (pin "20") (pinfunction "A7_20") (pintype "input"))
    )
    (net (code "13") (name "A8") (class "Default")
      (node (ref "U3") (pin "21") (pinfunction "A8_21") (pintype "input"))
      (node (ref "U4") (pin "K1") (pinfunction "IO_L37N_M3DQ1_3_K1") (pintype "bidirectional"))
      (node (ref "U9") (pin "21") (pinfunction "A8_21") (pintype "input"))
    )
    (net (code "14") (name "A9") (class "Default")
      (node (ref "U3") (pin "22") (pinfunction "A9_22") (pintype "input"))
      (node (ref "U4") (pin "K2") (pinfunction "IO_L37P_M3DQ0_3_K2") (pintype "bidirectional"))
      (node (ref "U9") (pin "22") (pinfunction "A9_22") (pintype "input"))
    )
    (net (code "15") (name "A10") (class "Default")
      (node (ref "U3") (pin "23") (pinfunction "A10_23") (pintype "input"))
      (node (ref "U4") (pin "D5") (pinfunction "IO_L3P_0_D5") (pintype "bidirectional"))
      (node (ref "U9") (pin "23") (pinfunction "A10_23") (pintype "input"))
    )
    (net (code "16") (name "A11") (class "Default")
      (node (ref "U3") (pin "24") (pinfunction "A11_24") (pintype "input"))
      (node (ref "U4") (pin "C5") (pinfunction "IO_L3N_0_C5") (pintype "bidirectional"))
      (node (ref "U9") (pin "24") (pinfunction "A11_24") (pintype "input"))
    )
    (net (code "17") (name "A12") (class "Default")
      (node (ref "U3") (pin "25") (pinfunction "A12_25") (pintype "input"))
      (node (ref "U4") (pin "A4") (pinfunction "IO_L1N_VREF_0_A4") (pintype "bidirectional"))
      (node (ref "U9") (pin "25") (pinfunction "A12_25") (pintype "input"))
    )
    (net (code "18") (name "A13") (class "Default")
      (node (ref "U3") (pin "26") (pinfunction "A13_26") (pintype "input"))
      (node (ref "U4") (pin "B5") (pinfunction "IO_L2P_0_B5") (pintype "bidirectional"))
      (node (ref "U9") (pin "26") (pinfunction "A13_26") (pintype "input"))
    )
    (net (code "19") (name "A14") (class "Default")
      (node (ref "U3") (pin "27") (pinfunction "A14_27") (pintype "input"))
      (node (ref "U4") (pin "A5") (pinfunction "IO_L2N_0_A5") (pintype "bidirectional"))
      (node (ref "U9") (pin "27") (pinfunction "A14_27") (pintype "input"))
    )
    (net (code "20") (name "A15") (class "Default")
      (node (ref "U3") (pin "42") (pinfunction "A15_42") (pintype "input"))
      (node (ref "U4") (pin "A6") (pinfunction "IO_L4N_0_A6") (pintype "bidirectional"))
      (node (ref "U9") (pin "42") (pinfunction "A15_42") (pintype "input"))
    )
    (net (code "21") (name "A16") (class "Default")
      (node (ref "U3") (pin "43") (pinfunction "A16_43") (pintype "input"))
      (node (ref "U4") (pin "C7") (pinfunction "IO_L6P_0_C7") (pintype "bidirectional"))
      (node (ref "U9") (pin "43") (pinfunction "A16_43") (pintype "input"))
    )
    (net (code "22") (name "A17") (class "Default")
      (node (ref "U3") (pin "44") (pinfunction "A17_44") (pintype "input"))
      (node (ref "U4") (pin "A7") (pinfunction "IO_L6N_0_A7") (pintype "bidirectional"))
      (node (ref "U9") (pin "44") (pinfunction "A17_44") (pintype "input"))
    )
    (net (code "23") (name "A18") (class "Default")
      (node (ref "U3") (pin "28") (pinfunction "A18/NC_28") (pintype "input"))
      (node (ref "U4") (pin "D6") (pinfunction "IO_L7P_0_D6") (pintype "bidirectional"))
      (node (ref "U9") (pin "28") (pinfunction "A18/NC_28") (pintype "input"))
    )
    (net (code "24") (name "AUDIO1") (class "Default")
      (node (ref "R35") (pin "1") (pinfunction "1_1") (pintype "passive"))
      (node (ref "U4") (pin "K15") (pinfunction "IO_L44P_A3_M1DQ6_1_K15") (pintype "bidirectional"))
    )
    (net (code "25") (name "AUDIO2") (class "Default")
      (node (ref "R36") (pin "1") (pinfunction "1_1") (pintype "passive"))
      (node (ref "U4") (pin "K16") (pinfunction "IO_L44N_A2_M1DQ7_1_K16") (pintype "bidirectional"))
    )
    (net (code "26") (name "BE0") (class "Default")
      (node (ref "U3") (pin "39") (pinfunction "~{BLE}_39") (pintype "input"))
      (node (ref "U4") (pin "B3") (pinfunction "IO_L83P_3_B3") (pintype "bidirectional"))
    )
    (net (code "27") (name "BE1") (class "Default")
      (node (ref "U3") (pin "40") (pinfunction "~{BHE}_40") (pintype "input"))
      (node (ref "U4") (pin "C3") (pinfunction "IO_L48P_M3BA0_3_C3") (pintype "bidirectional"))
    )
    (net (code "28") (name "BE2") (class "Default")
      (node (ref "U4") (pin "R1") (pinfunction "IO_L32N_M3DQ15_3_R1") (pintype "bidirectional"))
      (node (ref "U9") (pin "39") (pinfunction "~{BLE}_39") (pintype "input"))
    )
    (net (code "29") (name "BE3") (class "Default")
      (node (ref "U4") (pin "R2") (pinfunction "IO_L32P_M3DQ14_3_R2") (pintype "bidirectional"))
      (node (ref "U9") (pin "40") (pinfunction "~{BHE}_40") (pintype "input"))
    )
    (net (code "30") (name "BLUE") (class "Default")
      (node (ref "J6") (pin "3") (pinfunction "3_3") (pintype "passive"))
      (node (ref "R30") (pin "2") (pinfunction "2_2") (pintype "passive"))
      (node (ref "R31") (pin "2") (pinfunction "2_2") (pintype "passive"))
    )
    (net (code "31") (name "BLUE0") (class "Default")
      (node (ref "R30") (pin "1") (pinfunction "1_1") (pintype "passive"))
      (node (ref "U4") (pin "C13") (pinfunction "IO_L63P_SCP7_0_C13") (pintype "bidirectional"))
    )
    (net (code "32") (name "BLUE1") (class "Default")
      (node (ref "R31") (pin "1") (pinfunction "1_1") (pintype "passive"))
      (node (ref "U4") (pin "A13") (pinfunction "IO_L63N_SCP6_0_A13") (pintype "bidirectional"))
    )
    (net (code "33") (name "BUTTON") (class "Default")
      (node (ref "S2") (pin "3") (pinfunction "2_3") (pintype "passive"))
      (node (ref "U4") (pin "K14") (pinfunction "IO_L41N_GCLK8_M1CASN_1_K14") (pintype "bidirectional"))
    )
    (net (code "34") (name "CLK") (class "Default")
      (node (ref "J2") (pin "5") (pinfunction "SCK_5") (pintype "bidirectional"))
      (node (ref "U4") (pin "F13") (pinfunction "IO_L32P_A17_M1A8_1_F13") (pintype "bidirectional"))
    )
    (net (code "35") (name "CMD") (class "Default")
      (node (ref "J2") (pin "3") (pinfunction "DI_3") (pintype "bidirectional"))
      (node (ref "U4") (pin "F14") (pinfunction "IO_L32N_A16_M1A9_1_F14") (pintype "bidirectional"))
    )
    (net (code "36") (name "CS0") (class "Default")
      (node (ref "U3") (pin "6") (pinfunction "~{CS}_6") (pintype "input"))
      (node (ref "U4") (pin "H4") (pinfunction "IO_L44P_GCLK21_M3A5_3_H4") (pintype "bidirectional"))
    )
    (net (code "37") (name "CS1") (class "Default")
      (node (ref "U4") (pin "J4") (pinfunction "IO_L42N_GCLK24_M3LDM_3_J4") (pintype "bidirectional"))
      (node (ref "U9") (pin "6") (pinfunction "~{CS}_6") (pintype "input"))
    )
    (net (code "38") (name "CTS") (class "Default")
      (node (ref "U4") (pin "C16") (pinfunction "IO_L33N_A14_M1A4_1_C16") (pintype "bidirectional"))
      (node (ref "U7") (pin "41") (pinfunction "BDBUS3/CTS#/TMS/CS_41") (pintype "bidirectional"))
    )
    (net (code "39") (name "D0") (class "Default")
      (node (ref "U3") (pin "7") (pinfunction "D0_7") (pintype "bidirectional"))
      (node (ref "U4") (pin "E1") (pinfunction "IO_L46N_M3CLKN_3_E1") (pintype "bidirectional"))
    )
    (net (code "40") (name "D1") (class "Default")
      (node (ref "U3") (pin "8") (pinfunction "D1_8") (pintype "bidirectional"))
      (node (ref "U4") (pin "E2") (pinfunction "IO_L46P_M3CLK_3_E2") (pintype "bidirectional"))
    )
    (net (code "41") (name "D2") (class "Default")
      (node (ref "U3") (pin "9") (pinfunction "D2_9") (pintype "bidirectional"))
      (node (ref "U4") (pin "F1") (pinfunction "IO_L41N_GCLK26_M3DQ5_3_F1") (pintype "bidirectional"))
    )
    (net (code "42") (name "D3") (class "Default")
      (node (ref "U3") (pin "10") (pinfunction "D3_10") (pintype "bidirectional"))
      (node (ref "U4") (pin "F2") (pinfunction "IO_L41P_GCLK27_M3DQ4_3_F2") (pintype "bidirectional"))
    )
    (net (code "43") (name "D4") (class "Default")
      (node (ref "U3") (pin "13") (pinfunction "D4_13") (pintype "bidirectional"))
      (node (ref "U4") (pin "G1") (pinfunction "IO_L40N_M3DQ7_3_G1") (pintype "bidirectional"))
    )
    (net (code "44") (name "D5") (class "Default")
      (node (ref "U3") (pin "14") (pinfunction "D5_14") (pintype "bidirectional"))
      (node (ref "U4") (pin "G3") (pinfunction "IO_L40P_M3DQ6_3_G3") (pintype "bidirectional"))
    )
    (net (code "45") (name "D6") (class "Default")
      (node (ref "U3") (pin "15") (pinfunction "D6_15") (pintype "bidirectional"))
      (node (ref "U4") (pin "H1") (pinfunction "IO_L39N_M3LDQSN_3_H1") (pintype "bidirectional"))
    )
    (net (code "46") (name "D7") (class "Default")
      (node (ref "U3") (pin "16") (pinfunction "D7_16") (pintype "bidirectional"))
      (node (ref "U4") (pin "H2") (pinfunction "IO_L39P_M3LDQS_3_H2") (pintype "bidirectional"))
    )
    (net (code "47") (name "D8") (class "Default")
      (node (ref "U3") (pin "29") (pinfunction "D8_29") (pintype "bidirectional"))
      (node (ref "U4") (pin "A3") (pinfunction "IO_L83N_VREF_3_A3") (pintype "bidirectional"))
    )
    (net (code "48") (name "D9") (class "Default")
      (node (ref "U3") (pin "30") (pinfunction "D9_30") (pintype "bidirectional"))
      (node (ref "U4") (pin "A2") (pinfunction "IO_L52N_M3A9_3_A2") (pintype "bidirectional"))
    )
    (net (code "49") (name "D10") (class "Default")
      (node (ref "U3") (pin "31") (pinfunction "D10_31") (pintype "bidirectional"))
      (node (ref "U4") (pin "B1") (pinfunction "IO_L50N_M3BA2_3_B1") (pintype "bidirectional"))
    )
    (net (code "50") (name "D11") (class "Default")
      (node (ref "U3") (pin "32") (pinfunction "D11_32") (pintype "bidirectional"))
      (node (ref "U4") (pin "B2") (pinfunction "IO_L52P_M3A8_3_B2") (pintype "bidirectional"))
    )
    (net (code "51") (name "D12") (class "Default")
      (node (ref "U3") (pin "35") (pinfunction "D12_35") (pintype "bidirectional"))
      (node (ref "U4") (pin "C1") (pinfunction "IO_L50P_M3WE_3_C1") (pintype "bidirectional"))
    )
    (net (code "52") (name "D13") (class "Default")
      (node (ref "U3") (pin "36") (pinfunction "D13_36") (pintype "bidirectional"))
      (node (ref "U4") (pin "C2") (pinfunction "IO_L48N_M3BA1_3_C2") (pintype "bidirectional"))
    )
    (net (code "53") (name "D14") (class "Default")
      (node (ref "U3") (pin "37") (pinfunction "D14_37") (pintype "bidirectional"))
      (node (ref "U4") (pin "D1") (pinfunction "IO_L49N_M3A2_3_D1") (pintype "bidirectional"))
    )
    (net (code "54") (name "D15") (class "Default")
      (node (ref "U3") (pin "38") (pinfunction "D15_38") (pintype "bidirectional"))
      (node (ref "U4") (pin "D3") (pinfunction "IO_L49P_M3A7_3_D3") (pintype "bidirectional"))
    )
    (net (code "55") (name "D16") (class "Default")
      (node (ref "U4") (pin "P4") (pinfunction "IO_L63P_2_P4") (pintype "bidirectional"))
      (node (ref "U9") (pin "7") (pinfunction "D0_7") (pintype "bidirectional"))
    )
    (net (code "56") (name "D17") (class "Default")
      (node (ref "U4") (pin "T4") (pinfunction "IO_L63N_2_T4") (pintype "bidirectional"))
      (node (ref "U9") (pin "8") (pinfunction "D1_8") (pintype "bidirectional"))
    )
    (net (code "57") (name "D18") (class "Default")
      (node (ref "U4") (pin "R5") (pinfunction "IO_L48P_D7_2_R5") (pintype "bidirectional"))
      (node (ref "U9") (pin "9") (pinfunction "D2_9") (pintype "bidirectional"))
    )
    (net (code "58") (name "D19") (class "Default")
      (node (ref "U4") (pin "T5") (pinfunction "IO_L48N_RDWR_B_VREF_2_T5") (pintype "bidirectional"))
      (node (ref "U9") (pin "10") (pinfunction "D3_10") (pintype "bidirectional"))
    )
    (net (code "59") (name "D20") (class "Default")
      (node (ref "U4") (pin "P6") (pinfunction "IO_L47P_2_P6") (pintype "bidirectional"))
      (node (ref "U9") (pin "13") (pinfunction "D4_13") (pintype "bidirectional"))
    )
    (net (code "60") (name "D21") (class "Default")
      (node (ref "U4") (pin "T6") (pinfunction "IO_L47N_2_T6") (pintype "bidirectional"))
      (node (ref "U9") (pin "14") (pinfunction "D5_14") (pintype "bidirectional"))
    )
    (net (code "61") (name "D22") (class "Default")
      (node (ref "U4") (pin "R7") (pinfunction "IO_L32P_GCLK29_2_R7") (pintype "bidirectional"))
      (node (ref "U9") (pin "15") (pinfunction "D6_15") (pintype "bidirectional"))
    )
    (net (code "62") (name "D23") (class "Default")
      (node (ref "U4") (pin "T7") (pinfunction "IO_L32N_GCLK28_2_T7") (pintype "bidirectional"))
      (node (ref "U9") (pin "16") (pinfunction "D7_16") (pintype "bidirectional"))
    )
    (net (code "63") (name "D24") (class "Default")
      (node (ref "U4") (pin "L1") (pinfunction "IO_L36N_M3DQ9_3_L1") (pintype "bidirectional"))
      (node (ref "U9") (pin "29") (pinfunction "D8_29") (pintype "bidirectional"))
    )
    (net (code "64") (name "D25") (class "Default")
      (node (ref "U4") (pin "L3") (pinfunction "IO_L36P_M3DQ8_3_L3") (pintype "bidirectional"))
      (node (ref "U9") (pin "30") (pinfunction "D9_30") (pintype "bidirectional"))
    )
    (net (code "65") (name "D26") (class "Default")
      (node (ref "U4") (pin "M1") (pinfunction "IO_L35N_M3DQ11_3_M1") (pintype "bidirectional"))
      (node (ref "U9") (pin "31") (pinfunction "D10_31") (pintype "bidirectional"))
    )
    (net (code "66") (name "D27") (class "Default")
      (node (ref "U4") (pin "M2") (pinfunction "IO_L35P_M3DQ10_3_M2") (pintype "bidirectional"))
      (node (ref "U9") (pin "32") (pinfunction "D11_32") (pintype "bidirectional"))
    )
    (net (code "67") (name "D28") (class "Default")
      (node (ref "U4") (pin "N1") (pinfunction "IO_L34N_M3UDQSN_3_N1") (pintype "bidirectional"))
      (node (ref "U9") (pin "35") (pinfunction "D12_35") (pintype "bidirectional"))
    )
    (net (code "68") (name "D29") (class "Default")
      (node (ref "U4") (pin "N3") (pinfunction "IO_L34P_M3UDQS_3_N3") (pintype "bidirectional"))
      (node (ref "U9") (pin "36") (pinfunction "D13_36") (pintype "bidirectional"))
    )
    (net (code "69") (name "D30") (class "Default")
      (node (ref "U4") (pin "P1") (pinfunction "IO_L33N_M3DQ13_3_P1") (pintype "bidirectional"))
      (node (ref "U9") (pin "37") (pinfunction "D14_37") (pintype "bidirectional"))
    )
    (net (code "70") (name "D31") (class "Default")
      (node (ref "U4") (pin "P2") (pinfunction "IO_L33P_M3DQ12_3_P2") (pintype "bidirectional"))
      (node (ref "U9") (pin "38") (pinfunction "D15_38") (pintype "bidirectional"))
    )
    (net (code "71") (name "DAT0") (class "Default")
      (node (ref "J2") (pin "7") (pinfunction "DO_7") (pintype "bidirectional"))
      (node (ref "U4") (pin "H15") (pinfunction "IO_L37P_A7_M1A0_1_H15") (pintype "bidirectional"))
    )
    (net (code "72") (name "DAT1") (class "Default")
      (node (ref "J2") (pin "8") (pinfunction "RSV_8") (pintype "bidirectional"))
      (node (ref "U4") (pin "H16") (pinfunction "IO_L37N_A6_M1A1_1_H16") (pintype "bidirectional"))
    )
    (net (code "73") (name "DAT2") (class "Default")
      (node (ref "J2") (pin "1") (pinfunction "NC_1") (pintype "bidirectional"))
      (node (ref "U4") (pin "E12") (pinfunction "IO_L1N_A24_VREF_1_E12") (pintype "bidirectional"))
    )
    (net (code "74") (name "DAT3") (class "Default")
      (node (ref "J2") (pin "2") (pinfunction "CS_2") (pintype "bidirectional"))
      (node (ref "U4") (pin "E13") (pinfunction "IO_L1P_A25_1_E13") (pintype "bidirectional"))
    )
    (net (code "75") (name "DONE") (class "Default")
      (node (ref "R9") (pin "2") (pinfunction "2_2") (pintype "passive"))
      (node (ref "U4") (pin "P13") (pinfunction "DONE_2_P13") (pintype "bidirectional"))
    )
    (net (code "76") (name "EECLK") (class "Default")
      (node (ref "R4") (pin "1") (pinfunction "1_1") (pintype "passive"))
      (node (ref "U7") (pin "62") (pinfunction "EECLK_62") (pintype "bidirectional"))
      (node (ref "U8") (pin "4") (pinfunction "CLK_4") (pintype "input"))
    )
    (net (code "77") (name "EECS") (class "Default")
      (node (ref "R3") (pin "1") (pinfunction "1_1") (pintype "passive"))
      (node (ref "U7") (pin "63") (pinfunction "EECS_63") (pintype "bidirectional"))
      (node (ref "U8") (pin "5") (pinfunction "CS_5") (pintype "input"))
    )
    (net (code "78") (name "EEDATA") (class "Default")
      (node (ref "R6") (pin "2") (pinfunction "2_2") (pintype "passive"))
      (node (ref "U7") (pin "61") (pinfunction "EEDATA_61") (pintype "bidirectional"))
      (node (ref "U8") (pin "3") (pinfunction "DI_3") (pintype "input"))
    )
    (net (code "79") (name "FLASH_CS") (class "Default")
      (node (ref "R38") (pin "1") (pinfunction "1_1") (pintype "passive"))
      (node (ref "U2") (pin "1") (pinfunction "CS_1") (pintype "bidirectional"))
      (node (ref "U4") (pin "T3") (pinfunction "IO_L65N_CSO_B_2_T3") (pintype "bidirectional"))
    )
    (net (code "80") (name "FLASH_MISO0") (class "Default")
      (node (ref "U2") (pin "5") (pinfunction "MOSI_5") (pintype "bidirectional"))
      (node (ref "U4") (pin "T10") (pinfunction "IO_L3N_MOSI_CSI_B_MISO0_2_T10") (pintype "bidirectional"))
    )
    (net (code "81") (name "FLASH_MISO1") (class "Default")
      (node (ref "U2") (pin "2") (pinfunction "MISO_2") (pintype "bidirectional"))
      (node (ref "U4") (pin "P10") (pinfunction "IO_L3P_D0_DIN_MISO_MISO1_2_P10") (pintype "bidirectional"))
    )
    (net (code "82") (name "FLASH_MISO2") (class "Default")
      (node (ref "R39") (pin "1") (pinfunction "1_1") (pintype "passive"))
      (node (ref "U2") (pin "3") (pinfunction "WP_3") (pintype "bidirectional"))
      (node (ref "U4") (pin "N12") (pinfunction "IO_L12P_D1_MISO2_2_N12") (pintype "bidirectional"))
    )
    (net (code "83") (name "FLASH_MISO3") (class "Default")
      (node (ref "R40") (pin "1") (pinfunction "1_1") (pintype "passive"))
      (node (ref "U2") (pin "7") (pinfunction "HOLD_7") (pintype "bidirectional"))
      (node (ref "U4") (pin "P12") (pinfunction "IO_L12N_D2_MISO3_2_P12") (pintype "bidirectional"))
    )
    (net (code "84") (name "FLASH_SCK") (class "Default")
      (node (ref "U2") (pin "6") (pinfunction "SCK_6") (pintype "bidirectional"))
      (node (ref "U4") (pin "R11") (pinfunction "IO_L1P_CCLK_2_R11") (pintype "bidirectional"))
    )
    (net (code "85") (name "GND") (class "Default")
      (node (ref "C1") (pin "2") (pinfunction "2_2") (pintype "passive"))
      (node (ref "C10") (pin "2") (pinfunction "2_2") (pintype "passive"))
      (node (ref "C11") (pin "2") (pinfunction "2_2") (pintype "passive"))
      (node (ref "C12") (pin "2") (pinfunction "2_2") (pintype "passive"))
      (node (ref "C13") (pin "2") (pinfunction "2_2") (pintype "passive"))
      (node (ref "C14") (pin "2") (pinfunction "2_2") (pintype "passive"))
      (node (ref "C15") (pin "2") (pinfunction "2_2") (pintype "passive"))
      (node (ref "C16") (pin "2") (pinfunction "2_2") (pintype "passive"))
      (node (ref "C17") (pin "2") (pinfunction "2_2") (pintype "passive"))
      (node (ref "C18") (pin "2") (pinfunction "2_2") (pintype "passive"))
      (node (ref "C19") (pin "2") (pinfunction "2_2") (pintype "passive"))
      (node (ref "C2") (pin "2") (pinfunction "2_2") (pintype "passive"))
      (node (ref "C20") (pin "2") (pinfunction "2_2") (pintype "passive"))
      (node (ref "C21") (pin "2") (pinfunction "2_2") (pintype "passive"))
      (node (ref "C22") (pin "2") (pinfunction "2_2") (pintype "passive"))
      (node (ref "C23") (pin "2") (pinfunction "2_2") (pintype "passive"))
      (node (ref "C24") (pin "2") (pinfunction "2_2") (pintype "passive"))
      (node (ref "C25") (pin "2") (pinfunction "2_2") (pintype "passive"))
      (node (ref "C26") (pin "2") (pinfunction "2_2") (pintype "passive"))
      (node (ref "C27") (pin "2") (pinfunction "2_2") (pintype "passive"))
      (node (ref "C28") (pin "2") (pinfunction "2_2") (pintype "passive"))
      (node (ref "C29") (pin "2") (pinfunction "2_2") (pintype "passive"))
      (node (ref "C3") (pin "2") (pinfunction "2_2") (pintype "passive"))
      (node (ref "C30") (pin "2") (pinfunction "2_2") (pintype "passive"))
      (node (ref "C31") (pin "2") (pinfunction "2_2") (pintype "passive"))
      (node (ref "C32") (pin "2") (pinfunction "2_2") (pintype "passive"))
      (node (ref "C33") (pin "2") (pinfunction "2_2") (pintype "passive"))
      (node (ref "C34") (pin "2") (pinfunction "2_2") (pintype "passive"))
      (node (ref "C35") (pin "2") (pinfunction "2_2") (pintype "passive"))
      (node (ref "C36") (pin "2") (pinfunction "2_2") (pintype "passive"))
      (node (ref "C37") (pin "2") (pinfunction "2_2") (pintype "passive"))
      (node (ref "C4") (pin "2") (pinfunction "2_2") (pintype "passive"))
      (node (ref "C5") (pin "2") (pinfunction "2_2") (pintype "passive"))
      (node (ref "C6") (pin "2") (pinfunction "2_2") (pintype "passive"))
      (node (ref "C7") (pin "2") (pinfunction "2_2") (pintype "passive"))
      (node (ref "C8") (pin "2") (pinfunction "2_2") (pintype "passive"))
      (node (ref "C9") (pin "2") (pinfunction "2_2") (pintype "passive"))
      (node (ref "J1") (pin "2") (pinfunction "2_2") (pintype "passive"))
      (node (ref "J2") (pin "6") (pinfunction "GND_6") (pintype "bidirectional"))
      (node (ref "J2") (pin "GND1") (pinfunction "SHIELD_GND1") (pintype "bidirectional"))
      (node (ref "J2") (pin "GND3") (pinfunction "SHIELD_GND3") (pintype "bidirectional"))
      (node (ref "J3") (pin "SLEEVE") (pinfunction "SLEEVE_SLEEVE") (pintype "bidirectional"))
      (node (ref "J4") (pin "3") (pinfunction "3_3") (pintype "passive"))
      (node (ref "J5") (pin "3") (pinfunction "3_3") (pintype "passive"))
      (node (ref "J6") (pin "10") (pinfunction "10_10") (pintype "passive"))
      (node (ref "J6") (pin "11") (pinfunction "11_11") (pintype "passive"))
      (node (ref "J6") (pin "6") (pinfunction "6_6") (pintype "passive"))
      (node (ref "J6") (pin "7") (pinfunction "7_7") (pintype "passive"))
      (node (ref "J6") (pin "8") (pinfunction "8_8") (pintype "passive"))
      (node (ref "J7") (pin "1") (pinfunction "1_1") (pintype "passive"))
      (node (ref "J8") (pin "3") (pinfunction "3_3") (pintype "passive"))
      (node (ref "J8") (pin "4") (pinfunction "4_4") (pintype "passive"))
      (node (ref "J9") (pin "GND") (pinfunction "GND_GND") (pintype "bidirectional"))
      (node (ref "LD1") (pin "-") (pinfunction "C_-") (pintype "passive"))
      (node (ref "LD10") (pin "-") (pinfunction "C_-") (pintype "passive"))
      (node (ref "LD2") (pin "-") (pinfunction "C_-") (pintype "passive"))
      (node (ref "LD3") (pin "-") (pinfunction "C_-") (pintype "passive"))
      (node (ref "LD4") (pin "-") (pinfunction "C_-") (pintype "passive"))
      (node (ref "LD5") (pin "-") (pinfunction "C_-") (pintype "passive"))
      (node (ref "LD6") (pin "-") (pinfunction "C_-") (pintype "passive"))
      (node (ref "LD7") (pin "-") (pinfunction "C_-") (pintype "passive"))
      (node (ref "LD8") (pin "-") (pinfunction "C_-") (pintype "passive"))
      (node (ref "LD9") (pin "-") (pinfunction "C_-") (pintype "passive"))
      (node (ref "R10") (pin "2") (pinfunction "2_2") (pintype "passive"))
      (node (ref "R2") (pin "1") (pinfunction "1_1") (pintype "passive"))
      (node (ref "SV1") (pin "2") (pinfunction "2_2") (pintype "passive"))
      (node (ref "U1") (pin "2") (pinfunction "GND_2") (pintype "bidirectional"))
      (node (ref "U2") (pin "4") (pinfunction "GND_4") (pintype "bidirectional"))
      (node (ref "U3") (pin "12") (pinfunction "VSS_12") (pintype "input"))
      (node (ref "U3") (pin "34") (pinfunction "VSS_34") (pintype "input"))
      (node (ref "U4") (pin "A1") (pinfunction "GND_A1") (pintype "power_in"))
      (node (ref "U4") (pin "A16") (pinfunction "GND_A16") (pintype "power_in"))
      (node (ref "U4") (pin "B11") (pinfunction "GND_B11") (pintype "power_in"))
      (node (ref "U4") (pin "B7") (pinfunction "GND_B7") (pintype "power_in"))
      (node (ref "U4") (pin "D13") (pinfunction "GND_D13") (pintype "power_in"))
      (node (ref "U4") (pin "D4") (pinfunction "GND_D4") (pintype "power_in"))
      (node (ref "U4") (pin "E9") (pinfunction "GND_E9") (pintype "power_in"))
      (node (ref "U4") (pin "G15") (pinfunction "GND_G15") (pintype "power_in"))
      (node (ref "U4") (pin "G2") (pinfunction "GND_G2") (pintype "power_in"))
      (node (ref "U4") (pin "G8") (pinfunction "GND_G8") (pintype "power_in"))
      (node (ref "U4") (pin "H12") (pinfunction "GND_H12") (pintype "power_in"))
      (node (ref "U4") (pin "H7") (pinfunction "GND_H7") (pintype "power_in"))
      (node (ref "U4") (pin "H9") (pinfunction "GND_H9") (pintype "power_in"))
      (node (ref "U4") (pin "J5") (pinfunction "GND_J5") (pintype "power_in"))
      (node (ref "U4") (pin "J8") (pinfunction "GND_J8") (pintype "power_in"))
      (node (ref "U4") (pin "K7") (pinfunction "GND_K7") (pintype "power_in"))
      (node (ref "U4") (pin "K9") (pinfunction "GND_K9") (pintype "power_in"))
      (node (ref "U4") (pin "L15") (pinfunction "GND_L15") (pintype "power_in"))
      (node (ref "U4") (pin "L2") (pinfunction "GND_L2") (pintype "power_in"))
      (node (ref "U4") (pin "M8") (pinfunction "GND_M8") (pintype "power_in"))
      (node (ref "U4") (pin "N11") (pinfunction "IO_L13P_M1_2_N11") (pintype "bidirectional"))
      (node (ref "U4") (pin "N13") (pinfunction "GND_N13") (pintype "power_in"))
      (node (ref "U4") (pin "P3") (pinfunction "GND_P3") (pintype "power_in"))
      (node (ref "U4") (pin "R10") (pinfunction "GND_R10") (pintype "power_in"))
      (node (ref "U4") (pin "R6") (pinfunction "GND_R6") (pintype "power_in"))
      (node (ref "U4") (pin "T1") (pinfunction "GND_T1") (pintype "power_in"))
      (node (ref "U4") (pin "T16") (pinfunction "GND_T16") (pintype "power_in"))
      (node (ref "U5") (pin "1") (pinfunction "ADJ_1") (pintype "input"))
      (node (ref "U6") (pin "1") (pinfunction "ADJ_1") (pintype "input"))
      (node (ref "U7") (pin "1") (pinfunction "GND0_1") (pintype "bidirectional"))
      (node (ref "U7") (pin "10") (pinfunction "AGND_10") (pintype "bidirectional"))
      (node (ref "U7") (pin "11") (pinfunction "GND2_11") (pintype "bidirectional"))
      (node (ref "U7") (pin "13") (pinfunction "TEST_13") (pintype "bidirectional"))
      (node (ref "U7") (pin "15") (pinfunction "GND3_15") (pintype "bidirectional"))
      (node (ref "U7") (pin "25") (pinfunction "GND4_25") (pintype "bidirectional"))
      (node (ref "U7") (pin "35") (pinfunction "GND5_35") (pintype "bidirectional"))
      (node (ref "U7") (pin "47") (pinfunction "GND6_47") (pintype "bidirectional"))
      (node (ref "U7") (pin "5") (pinfunction "GND1_5") (pintype "bidirectional"))
      (node (ref "U7") (pin "51") (pinfunction "GND7_51") (pintype "bidirectional"))
      (node (ref "U8") (pin "2") (pinfunction "GND_2") (pintype "power_in"))
      (node (ref "U9") (pin "12") (pinfunction "VSS_12") (pintype "input"))
      (node (ref "U9") (pin "34") (pinfunction "VSS_34") (pintype "input"))
    )
    (net (code "86") (name "GREEN") (class "Default")
      (node (ref "J6") (pin "2") (pinfunction "2_2") (pintype "passive"))
      (node (ref "R27") (pin "2") (pinfunction "2_2") (pintype "passive"))
      (node (ref "R28") (pin "2") (pinfunction "2_2") (pintype "passive"))
      (node (ref "R29") (pin "2") (pinfunction "2_2") (pintype "passive"))
    )
    (net (code "87") (name "GREEN0") (class "Default")
      (node (ref "R27") (pin "1") (pinfunction "1_1") (pintype "passive"))
      (node (ref "U4") (pin "A11") (pinfunction "IO_L39N_0_A11") (pintype "bidirectional"))
    )
    (net (code "88") (name "GREEN1") (class "Default")
      (node (ref "R28") (pin "1") (pinfunction "1_1") (pintype "passive"))
      (node (ref "U4") (pin "B12") (pinfunction "IO_L62P_0_B12") (pintype "bidirectional"))
    )
    (net (code "89") (name "GREEN2") (class "Default")
      (node (ref "R29") (pin "1") (pinfunction "1_1") (pintype "passive"))
      (node (ref "U4") (pin "A12") (pinfunction "IO_L62N_VREF_0_A12") (pintype "bidirectional"))
    )
    (net (code "90") (name "HS") (class "Default")
      (node (ref "J6") (pin "13") (pinfunction "13_13") (pintype "passive"))
      (node (ref "R33") (pin "2") (pinfunction "2_2") (pintype "passive"))
    )
    (net (code "91") (name "HSYNC") (class "Default")
      (node (ref "R33") (pin "1") (pinfunction "1_1") (pintype "passive"))
      (node (ref "U4") (pin "D11") (pinfunction "IO_L66P_SCP1_0_D11") (pintype "bidirectional"))
    )
    (net (code "92") (name "INIT_B") (class "Default")
      (node (ref "R8") (pin "2") (pinfunction "2_2") (pintype "passive"))
      (node (ref "U4") (pin "R3") (pinfunction "IO_L65P_INIT_B_2_R3") (pintype "bidirectional"))
    )
    (net (code "93") (name "IO1N") (class "Default")
      (node (ref "J8") (pin "5") (pinfunction "5_5") (pintype "passive"))
      (node (ref "U4") (pin "P5") (pinfunction "IO_L49N_D4_2_P5") (pintype "bidirectional"))
    )
    (net (code "94") (name "IO1P") (class "Default")
      (node (ref "J8") (pin "6") (pinfunction "6_6") (pintype "passive"))
      (node (ref "U4") (pin "N5") (pinfunction "IO_L49P_D3_2_N5") (pintype "bidirectional"))
    )
    (net (code "95") (name "IO2N") (class "Default")
      (node (ref "J8") (pin "7") (pinfunction "7_7") (pintype "passive"))
      (node (ref "U4") (pin "N6") (pinfunction "IO_L64N_D9_2_N6") (pintype "bidirectional"))
    )
    (net (code "96") (name "IO2P") (class "Default")
      (node (ref "J8") (pin "8") (pinfunction "8_8") (pintype "passive"))
      (node (ref "U4") (pin "M6") (pinfunction "IO_L64P_D8_2_M6") (pintype "bidirectional"))
    )
    (net (code "97") (name "IO3N") (class "Default")
      (node (ref "J8") (pin "9") (pinfunction "9_9") (pintype "passive"))
      (node (ref "U4") (pin "M7") (pinfunction "IO_L31N_GCLK30_D15_2_M7") (pintype "bidirectional"))
    )
    (net (code "98") (name "IO3P") (class "Default")
      (node (ref "J8") (pin "10") (pinfunction "10_10") (pintype "passive"))
      (node (ref "U4") (pin "P7") (pinfunction "IO_L31P_GCLK31_D14_2_P7") (pintype "bidirectional"))
    )
    (net (code "99") (name "IO4N") (class "Default")
      (node (ref "J8") (pin "11") (pinfunction "11_11") (pintype "passive"))
      (node (ref "U4") (pin "T8") (pinfunction "IO_L30N_GCLK0_USERCCLK_2_T8") (pintype "bidirectional"))
    )
    (net (code "100") (name "IO4P") (class "Default")
      (node (ref "J8") (pin "12") (pinfunction "12_12") (pintype "passive"))
      (node (ref "U4") (pin "P8") (pinfunction "IO_L30P_GCLK1_D13_2_P8") (pintype "bidirectional"))
    )
    (net (code "101") (name "IO5N") (class "Default")
      (node (ref "J8") (pin "13") (pinfunction "13_13") (pintype "passive"))
      (node (ref "U4") (pin "T9") (pinfunction "IO_L23N_2_T9") (pintype "bidirectional"))
    )
    (net (code "102") (name "IO5P") (class "Default")
      (node (ref "J8") (pin "14") (pinfunction "14_14") (pintype "passive"))
      (node (ref "U4") (pin "R9") (pinfunction "IO_L23P_2_R9") (pintype "bidirectional"))
    )
    (net (code "103") (name "IO6N") (class "Default")
      (node (ref "J8") (pin "15") (pinfunction "15_15") (pintype "passive"))
      (node (ref "U4") (pin "N8") (pinfunction "IO_L29N_GCLK2_2_N8") (pintype "bidirectional"))
    )
    (net (code "104") (name "IO6P") (class "Default")
      (node (ref "J8") (pin "16") (pinfunction "16_16") (pintype "passive"))
      (node (ref "U4") (pin "M9") (pinfunction "IO_L29P_GCLK3_2_M9") (pintype "bidirectional"))
    )
    (net (code "105") (name "IO7N") (class "Default")
      (node (ref "J8") (pin "17") (pinfunction "17_17") (pintype "passive"))
      (node (ref "U4") (pin "M10") (pinfunction "IO_L16N_VREF_2_M10") (pintype "bidirectional"))
    )
    (net (code "106") (name "IO7P") (class "Default")
      (node (ref "J8") (pin "18") (pinfunction "18_18") (pintype "passive"))
      (node (ref "U4") (pin "L10") (pinfunction "IO_L16P_2_L10") (pintype "bidirectional"))
    )
    (net (code "107") (name "IO8N") (class "Default")
      (node (ref "J8") (pin "19") (pinfunction "19_19") (pintype "passive"))
      (node (ref "U4") (pin "T15") (pinfunction "IO_L50N_M1UDQSN_1_T15") (pintype "bidirectional"))
    )
    (net (code "108") (name "IO8P") (class "Default")
      (node (ref "J8") (pin "20") (pinfunction "20_20") (pintype "passive"))
      (node (ref "U4") (pin "R14") (pinfunction "IO_L50P_M1UDQS_1_R14") (pintype "bidirectional"))
    )
    (net (code "109") (name "IRQ") (class "Default")
      (node (ref "J1") (pin "8") (pinfunction "8_8") (pintype "passive"))
      (node (ref "J7") (pin "8") (pinfunction "8_8") (pintype "passive"))
      (node (ref "U4") (pin "A14") (pinfunction "IO_L65N_SCP2_0_A14") (pintype "bidirectional"))
    )
    (net (code "110") (name "LED1") (class "Default")
      (node (ref "R14") (pin "2") (pinfunction "2_2") (pintype "passive"))
      (node (ref "U4") (pin "N16") (pinfunction "IO_L45N_A0_M1LDQSN_1_N16") (pintype "bidirectional"))
    )
    (net (code "111") (name "LED2") (class "Default")
      (node (ref "R15") (pin "2") (pinfunction "2_2") (pintype "passive"))
      (node (ref "U4") (pin "N14") (pinfunction "IO_L45P_A1_M1LDQS_1_N14") (pintype "bidirectional"))
    )
    (net (code "112") (name "LED3") (class "Default")
      (node (ref "R17") (pin "2") (pinfunction "2_2") (pintype "passive"))
      (node (ref "U4") (pin "M14") (pinfunction "IO_L74N_DOUT_BUSY_1_M14") (pintype "bidirectional"))
    )
    (net (code "113") (name "LED4") (class "Default")
      (node (ref "R18") (pin "2") (pinfunction "2_2") (pintype "passive"))
      (node (ref "U4") (pin "M13") (pinfunction "IO_L74P_AWAKE_1_M13") (pintype "bidirectional"))
    )
    (net (code "114") (name "LED5") (class "Default")
      (node (ref "R19") (pin "2") (pinfunction "2_2") (pintype "passive"))
      (node (ref "U4") (pin "L12") (pinfunction "IO_L53P_1_L12") (pintype "bidirectional"))
    )
    (net (code "115") (name "LED6") (class "Default")
      (node (ref "R20") (pin "2") (pinfunction "2_2") (pintype "passive"))
      (node (ref "U4") (pin "L13") (pinfunction "IO_L53N_VREF_1_L13") (pintype "bidirectional"))
    )
    (net (code "116") (name "LED7") (class "Default")
      (node (ref "R21") (pin "2") (pinfunction "2_2") (pintype "passive"))
      (node (ref "U4") (pin "L14") (pinfunction "IO_L47P_FWE_B_M1DQ0_1_L14") (pintype "bidirectional"))
    )
    (net (code "117") (name "LED8") (class "Default")
      (node (ref "R22") (pin "2") (pinfunction "2_2") (pintype "passive"))
      (node (ref "U4") (pin "L16") (pinfunction "IO_L47N_LDC_M1DQ1_1_L16") (pintype "bidirectional"))
    )
    (net (code "118") (name "MISO") (class "Default")
      (node (ref "J1") (pin "5") (pinfunction "5_5") (pintype "passive"))
      (node (ref "J7") (pin "7") (pinfunction "7_7") (pintype "passive"))
      (node (ref "U4") (pin "C10") (pinfunction "IO_L37N_GCLK12_0_C10") (pintype "bidirectional"))
    )
    (net (code "119") (name "MOSI") (class "Default")
      (node (ref "J1") (pin "6") (pinfunction "6_6") (pintype "passive"))
      (node (ref "J7") (pin "6") (pinfunction "6_6") (pintype "passive"))
      (node (ref "U4") (pin "D8") (pinfunction "IO_L38P_0_D8") (pintype "bidirectional"))
    )
    (net (code "120") (name "NE") (class "Default")
      (node (ref "J1") (pin "1") (pinfunction "1_1") (pintype "passive"))
      (node (ref "J7") (pin "3") (pinfunction "3_3") (pintype "passive"))
      (node (ref "U4") (pin "C8") (pinfunction "IO_L38N_VREF_0_C8") (pintype "bidirectional"))
    )
    (net (code "121") (name "Net-(C34-Pad1)") (class "Default")
      (node (ref "C34") (pin "1") (pinfunction "1_1") (pintype "passive"))
      (node (ref "J3") (pin "RING") (pinfunction "RING_RING") (pintype "bidirectional"))
      (node (ref "R36") (pin "2") (pinfunction "2_2") (pintype "passive"))
    )
    (net (code "122") (name "Net-(C35-Pad1)") (class "Default")
      (node (ref "C35") (pin "1") (pinfunction "1_1") (pintype "passive"))
      (node (ref "J3") (pin "TIP") (pinfunction "TIP_TIP") (pintype "bidirectional"))
      (node (ref "R35") (pin "2") (pinfunction "2_2") (pintype "passive"))
    )
    (net (code "123") (name "Net-(J2-VCC)") (class "Default")
      (node (ref "C31") (pin "1") (pinfunction "1_1") (pintype "passive"))
      (node (ref "J2") (pin "4") (pinfunction "VCC_4") (pintype "bidirectional"))
      (node (ref "L3") (pin "1") (pinfunction "1_1") (pintype "passive"))
    )
    (net (code "124") (name "Net-(J4-Pad1)") (class "Default")
      (node (ref "J4") (pin "1") (pinfunction "1_1") (pintype "passive"))
      (node (ref "R7") (pin "2") (pinfunction "2_2") (pintype "passive"))
    )
    (net (code "125") (name "Net-(J4-Pad5)") (class "Default")
      (node (ref "J4") (pin "5") (pinfunction "5_5") (pintype "passive"))
      (node (ref "R12") (pin "2") (pinfunction "2_2") (pintype "passive"))
    )
    (net (code "126") (name "Net-(J5-Pad1)") (class "Default")
      (node (ref "J5") (pin "1") (pinfunction "1_1") (pintype "passive"))
      (node (ref "R11") (pin "2") (pinfunction "2_2") (pintype "passive"))
    )
    (net (code "127") (name "Net-(J5-Pad5)") (class "Default")
      (node (ref "J5") (pin "5") (pinfunction "5_5") (pintype "passive"))
      (node (ref "R13") (pin "2") (pinfunction "2_2") (pintype "passive"))
    )
    (net (code "128") (name "Net-(LD1-A)") (class "Default")
      (node (ref "LD1") (pin "+") (pinfunction "A_+") (pintype "passive"))
      (node (ref "R14") (pin "1") (pinfunction "1_1") (pintype "passive"))
    )
    (net (code "129") (name "Net-(LD2-A)") (class "Default")
      (node (ref "LD2") (pin "+") (pinfunction "A_+") (pintype "passive"))
      (node (ref "R15") (pin "1") (pinfunction "1_1") (pintype "passive"))
    )
    (net (code "130") (name "Net-(LD3-A)") (class "Default")
      (node (ref "LD3") (pin "+") (pinfunction "A_+") (pintype "passive"))
      (node (ref "R17") (pin "1") (pinfunction "1_1") (pintype "passive"))
    )
    (net (code "131") (name "Net-(LD4-A)") (class "Default")
      (node (ref "LD4") (pin "+") (pinfunction "A_+") (pintype "passive"))
      (node (ref "R18") (pin "1") (pinfunction "1_1") (pintype "passive"))
    )
    (net (code "132") (name "Net-(LD5-A)") (class "Default")
      (node (ref "LD5") (pin "+") (pinfunction "A_+") (pintype "passive"))
      (node (ref "R19") (pin "1") (pinfunction "1_1") (pintype "passive"))
    )
    (net (code "133") (name "Net-(LD6-A)") (class "Default")
      (node (ref "LD6") (pin "+") (pinfunction "A_+") (pintype "passive"))
      (node (ref "R20") (pin "1") (pinfunction "1_1") (pintype "passive"))
    )
    (net (code "134") (name "Net-(LD7-A)") (class "Default")
      (node (ref "LD7") (pin "+") (pinfunction "A_+") (pintype "passive"))
      (node (ref "R21") (pin "1") (pinfunction "1_1") (pintype "passive"))
    )
    (net (code "135") (name "Net-(LD8-A)") (class "Default")
      (node (ref "LD8") (pin "+") (pinfunction "A_+") (pintype "passive"))
      (node (ref "R22") (pin "1") (pinfunction "1_1") (pintype "passive"))
    )
    (net (code "136") (name "Net-(LD9-A)") (class "Default")
      (node (ref "LD9") (pin "+") (pinfunction "A_+") (pintype "passive"))
      (node (ref "R16") (pin "1") (pinfunction "1_1") (pintype "passive"))
    )
    (net (code "137") (name "Net-(LD10-A)") (class "Default")
      (node (ref "LD10") (pin "+") (pinfunction "A_+") (pintype "passive"))
      (node (ref "R34") (pin "1") (pinfunction "1_1") (pintype "passive"))
    )
    (net (code "138") (name "Net-(LD11-C)") (class "Default")
      (node (ref "LD11") (pin "-") (pinfunction "C_-") (pintype "passive"))
      (node (ref "R9") (pin "1") (pinfunction "1_1") (pintype "passive"))
    )
    (net (code "139") (name "Net-(U4A-IO_L1P_HSWAPEN_0)") (class "Default")
      (node (ref "R10") (pin "1") (pinfunction "1_1") (pintype "passive"))
      (node (ref "U4") (pin "C4") (pinfunction "IO_L1P_HSWAPEN_0_C4") (pintype "bidirectional"))
    )
    (net (code "140") (name "Net-(U7-DM)") (class "Default")
      (node (ref "J9") (pin "D-") (pinfunction "D-_D-") (pintype "bidirectional"))
      (node (ref "U7") (pin "7") (pinfunction "DM_7") (pintype "bidirectional"))
    )
    (net (code "141") (name "Net-(U7-DP)") (class "Default")
      (node (ref "J9") (pin "D+") (pinfunction "D+_D+") (pintype "bidirectional"))
      (node (ref "U7") (pin "8") (pinfunction "DP_8") (pintype "bidirectional"))
    )
    (net (code "142") (name "Net-(U7-OSC0)") (class "Default")
      (node (ref "C10") (pin "1") (pinfunction "1_1") (pintype "passive"))
      (node (ref "U7") (pin "3") (pinfunction "OSC0_3") (pintype "bidirectional"))
      (node (ref "X1") (pin "3") (pinfunction "2_3") (pintype "passive"))
    )
    (net (code "143") (name "Net-(U7-OSCI)") (class "Default")
      (node (ref "C9") (pin "1") (pinfunction "1_1") (pintype "passive"))
      (node (ref "U7") (pin "2") (pinfunction "OSCI_2") (pintype "bidirectional"))
      (node (ref "X1") (pin "1") (pinfunction "1_1") (pintype "passive"))
    )
    (net (code "144") (name "Net-(U7-REF)") (class "Default")
      (node (ref "R2") (pin "2") (pinfunction "2_2") (pintype "passive"))
      (node (ref "U7") (pin "6") (pinfunction "REF_6") (pintype "bidirectional"))
    )
    (net (code "145") (name "Net-(U7-RESET#)") (class "Default")
      (node (ref "R1") (pin "2") (pinfunction "2_2") (pintype "passive"))
      (node (ref "U7") (pin "14") (pinfunction "RESET#_14") (pintype "bidirectional"))
    )
    (net (code "146") (name "Net-(U7-VPHY)") (class "Default")
      (node (ref "C12") (pin "1") (pinfunction "1_1") (pintype "passive"))
      (node (ref "C13") (pin "1") (pinfunction "1_1") (pintype "passive"))
      (node (ref "L1") (pin "1") (pinfunction "1_1") (pintype "passive"))
      (node (ref "U7") (pin "4") (pinfunction "VPHY_4") (pintype "bidirectional"))
    )
    (net (code "147") (name "Net-(U7-VPLL)") (class "Default")
      (node (ref "C14") (pin "1") (pinfunction "1_1") (pintype "passive"))
      (node (ref "C15") (pin "1") (pinfunction "1_1") (pintype "passive"))
      (node (ref "L2") (pin "1") (pinfunction "1_1") (pintype "passive"))
      (node (ref "U7") (pin "9") (pinfunction "VPLL_9") (pintype "bidirectional"))
    )
    (net (code "148") (name "Net-(U8-DO)") (class "Default")
      (node (ref "R5") (pin "1") (pinfunction "1_1") (pintype "passive"))
      (node (ref "R6") (pin "1") (pinfunction "1_1") (pintype "passive"))
      (node (ref "U8") (pin "1") (pinfunction "DO_1") (pintype "output"))
    )
    (net (code "149") (name "OE") (class "Default")
      (node (ref "U3") (pin "41") (pinfunction "~{OE}_41") (pintype "input"))
      (node (ref "U4") (pin "B6") (pinfunction "IO_L4P_0_B6") (pintype "bidirectional"))
      (node (ref "U9") (pin "41") (pinfunction "~{OE}_41") (pintype "input"))
    )
    (net (code "150") (name "OSC_IN") (class "Default")
      (node (ref "U1") (pin "3") (pinfunction "OUT_3") (pintype "bidirectional"))
      (node (ref "U4") (pin "J16") (pinfunction "IO_L43N_GCLK4_M1DQ5_1_J16") (pintype "bidirectional"))
    )
    (net (code "151") (name "PMOD2-IO1") (class "Default")
      (node (ref "R7") (pin "1") (pinfunction "1_1") (pintype "passive"))
      (node (ref "U4") (pin "A8") (pinfunction "IO_L33N_0_A8") (pintype "bidirectional"))
    )
    (net (code "152") (name "PMOD2-IO2") (class "Default")
      (node (ref "R11") (pin "1") (pinfunction "1_1") (pintype "passive"))
      (node (ref "U4") (pin "A9") (pinfunction "IO_L34N_GCLK18_0_A9") (pintype "bidirectional"))
    )
    (net (code "153") (name "PMOD2-IO3") (class "Default")
      (node (ref "R12") (pin "1") (pinfunction "1_1") (pintype "passive"))
      (node (ref "U4") (pin "B8") (pinfunction "IO_L33P_0_B8") (pintype "bidirectional"))
    )
    (net (code "154") (name "PMOD2-IO4") (class "Default")
      (node (ref "R13") (pin "1") (pinfunction "1_1") (pintype "passive"))
      (node (ref "U4") (pin "C9") (pinfunction "IO_L34P_GCLK19_0_C9") (pintype "bidirectional"))
    )
    (net (code "155") (name "PROGRAM_B") (class "Default")
      (node (ref "R23") (pin "2") (pinfunction "2_2") (pintype "passive"))
      (node (ref "U4") (pin "T2") (pinfunction "PROGRAM_B_2_T2") (pintype "input"))
    )
    (net (code "156") (name "PU") (class "Default")
      (node (ref "R37") (pin "2") (pinfunction "2_2") (pintype "passive"))
      (node (ref "S1") (pin "1") (pinfunction "1_1") (pintype "passive"))
      (node (ref "S1") (pin "2") (pinfunction "2_2") (pintype "passive"))
      (node (ref "S1") (pin "3") (pinfunction "3_3") (pintype "passive"))
      (node (ref "S1") (pin "4") (pinfunction "4_4") (pintype "passive"))
      (node (ref "S1") (pin "5") (pinfunction "5_5") (pintype "passive"))
      (node (ref "S1") (pin "6") (pinfunction "6_6") (pintype "passive"))
      (node (ref "S1") (pin "7") (pinfunction "7_7") (pintype "passive"))
      (node (ref "S1") (pin "8") (pinfunction "8_8") (pintype "passive"))
    )
    (net (code "157") (name "RED") (class "Default")
      (node (ref "J6") (pin "1") (pinfunction "1_1") (pintype "passive"))
      (node (ref "R24") (pin "2") (pinfunction "2_2") (pintype "passive"))
      (node (ref "R25") (pin "2") (pinfunction "2_2") (pintype "passive"))
      (node (ref "R26") (pin "2") (pinfunction "2_2") (pintype "passive"))
    )
    (net (code "158") (name "RED0") (class "Default")
      (node (ref "R24") (pin "1") (pinfunction "1_1") (pintype "passive"))
      (node (ref "U4") (pin "B10") (pinfunction "IO_L35P_GCLK17_0_B10") (pintype "bidirectional"))
    )
    (net (code "159") (name "RED1") (class "Default")
      (node (ref "R25") (pin "1") (pinfunction "1_1") (pintype "passive"))
      (node (ref "U4") (pin "A10") (pinfunction "IO_L35N_GCLK16_0_A10") (pintype "bidirectional"))
    )
    (net (code "160") (name "RED2") (class "Default")
      (node (ref "R26") (pin "1") (pinfunction "1_1") (pintype "passive"))
      (node (ref "U4") (pin "C11") (pinfunction "IO_L39P_0_C11") (pintype "bidirectional"))
    )
    (net (code "161") (name "RTS") (class "Default")
      (node (ref "U4") (pin "C15") (pinfunction "IO_L33P_A15_M1A10_1_C15") (pintype "bidirectional"))
      (node (ref "U7") (pin "40") (pinfunction "BDBUS2/RTS#/TDO/DI_40") (pintype "bidirectional"))
    )
    (net (code "162") (name "RXD") (class "Default")
      (node (ref "U4") (pin "B15") (pinfunction "IO_L29P_A23_M1A13_1_B15") (pintype "bidirectional"))
      (node (ref "U7") (pin "38") (pinfunction "BDBUS0/TXD/TCK/SK_38") (pintype "bidirectional"))
    )
    (net (code "163") (name "SCK") (class "Default")
      (node (ref "J1") (pin "3") (pinfunction "3_3") (pintype "passive"))
      (node (ref "J7") (pin "5") (pinfunction "5_5") (pintype "passive"))
      (node (ref "U4") (pin "D9") (pinfunction "IO_L40N_0_D9") (pintype "bidirectional"))
    )
    (net (code "164") (name "SD-DET") (class "Default")
      (node (ref "J2") (pin "CD1") (pinfunction "SHIELD_CD1") (pintype "bidirectional"))
      (node (ref "U4") (pin "J14") (pinfunction "IO_L43P_GCLK5_M1DQ4_1_J14") (pintype "bidirectional"))
    )
    (net (code "165") (name "SD-LED") (class "Default")
      (node (ref "R34") (pin "2") (pinfunction "2_2") (pintype "passive"))
      (node (ref "U4") (pin "H13") (pinfunction "IO_L39P_M1A3_1_H13") (pintype "bidirectional"))
    )
    (net (code "166") (name "SS") (class "Default")
      (node (ref "J1") (pin "4") (pinfunction "4_4") (pintype "passive"))
      (node (ref "J7") (pin "4") (pinfunction "4_4") (pintype "passive"))
      (node (ref "U4") (pin "F9") (pinfunction "IO_L40P_0_F9") (pintype "bidirectional"))
    )
    (net (code "167") (name "SW1") (class "Default")
      (node (ref "S1") (pin "9") (pinfunction "9_9") (pintype "passive"))
      (node (ref "U4") (pin "G14") (pinfunction "IO_L36P_A9_M1BA0_1_G14") (pintype "bidirectional"))
    )
    (net (code "168") (name "SW2") (class "Default")
      (node (ref "S1") (pin "10") (pinfunction "10_10") (pintype "passive"))
      (node (ref "U4") (pin "G16") (pinfunction "IO_L36N_A8_M1BA1_1_G16") (pintype "bidirectional"))
    )
    (net (code "169") (name "SW3") (class "Default")
      (node (ref "S1") (pin "11") (pinfunction "11_11") (pintype "passive"))
      (node (ref "U4") (pin "F15") (pinfunction "IO_L35P_A11_M1A7_1_F15") (pintype "bidirectional"))
    )
    (net (code "170") (name "SW4") (class "Default")
      (node (ref "S1") (pin "12") (pinfunction "12_12") (pintype "passive"))
      (node (ref "U4") (pin "F16") (pinfunction "IO_L35N_A10_M1A2_1_F16") (pintype "bidirectional"))
    )
    (net (code "171") (name "SW5") (class "Default")
      (node (ref "S1") (pin "13") (pinfunction "13_13") (pintype "passive"))
      (node (ref "U4") (pin "E15") (pinfunction "IO_L34P_A13_M1WE_1_E15") (pintype "bidirectional"))
    )
    (net (code "172") (name "SW6") (class "Default")
      (node (ref "S1") (pin "14") (pinfunction "14_14") (pintype "passive"))
      (node (ref "U4") (pin "E16") (pinfunction "IO_L34N_A12_M1BA2_1_E16") (pintype "bidirectional"))
    )
    (net (code "173") (name "SW7") (class "Default")
      (node (ref "S1") (pin "15") (pinfunction "15_15") (pintype "passive"))
      (node (ref "U4") (pin "D14") (pinfunction "IO_L31P_A19_M1CKE_1_D14") (pintype "bidirectional"))
    )
    (net (code "174") (name "SW8") (class "Default")
      (node (ref "S1") (pin "16") (pinfunction "16_16") (pintype "passive"))
      (node (ref "U4") (pin "D16") (pinfunction "IO_L31N_A18_M1A12_1_D16") (pintype "bidirectional"))
    )
    (net (code "175") (name "TCK") (class "Default")
      (node (ref "SV1") (pin "3") (pinfunction "3_3") (pintype "passive"))
      (node (ref "U4") (pin "C14") (pinfunction "TCK_C14") (pintype "input"))
      (node (ref "U7") (pin "16") (pinfunction "ADBUS0/TXD/TCK/SK_16") (pintype "bidirectional"))
    )
    (net (code "176") (name "TDI") (class "Default")
      (node (ref "SV1") (pin "5") (pinfunction "5_5") (pintype "passive"))
      (node (ref "U4") (pin "C12") (pinfunction "TDI_C12") (pintype "input"))
      (node (ref "U7") (pin "17") (pinfunction "ADBUS1/RXD/TDI/DO_17") (pintype "bidirectional"))
    )
    (net (code "177") (name "TDO") (class "Default")
      (node (ref "SV1") (pin "4") (pinfunction "4_4") (pintype "passive"))
      (node (ref "U4") (pin "E14") (pinfunction "TDO_E14") (pintype "output"))
      (node (ref "U7") (pin "18") (pinfunction "ADBUS2/RTS#/TDO/DI_18") (pintype "bidirectional"))
    )
    (net (code "178") (name "TMS") (class "Default")
      (node (ref "SV1") (pin "6") (pinfunction "6_6") (pintype "passive"))
      (node (ref "U4") (pin "A15") (pinfunction "TMS_A15") (pintype "input"))
      (node (ref "U7") (pin "19") (pinfunction "ADBUS3/CTS#/TMS/CS_19") (pintype "bidirectional"))
    )
    (net (code "179") (name "TXD") (class "Default")
      (node (ref "U4") (pin "B16") (pinfunction "IO_L29N_A22_M1A14_1_B16") (pintype "bidirectional"))
      (node (ref "U7") (pin "39") (pinfunction "BDBUS1/RXD/TDI/DO_39") (pintype "bidirectional"))
    )
    (net (code "180") (name "VBUS") (class "Default")
      (node (ref "F1") (pin "1") (pinfunction "1_1") (pintype "bidirectional"))
      (node (ref "J9") (pin "VBUS") (pinfunction "VBUS_VBUS") (pintype "bidirectional"))
    )
    (net (code "181") (name "VS") (class "Default")
      (node (ref "J6") (pin "14") (pinfunction "14_14") (pintype "passive"))
      (node (ref "R32") (pin "2") (pinfunction "2_2") (pintype "passive"))
    )
    (net (code "182") (name "VSYNC") (class "Default")
      (node (ref "R32") (pin "1") (pinfunction "1_1") (pintype "passive"))
      (node (ref "U4") (pin "E11") (pinfunction "IO_L64N_SCP4_0_E11") (pintype "bidirectional"))
    )
    (net (code "183") (name "WE") (class "Default")
      (node (ref "U3") (pin "17") (pinfunction "~{WE}_17") (pintype "input"))
      (node (ref "U4") (pin "J1") (pinfunction "IO_L38N_M3DQ3_3_J1") (pintype "bidirectional"))
      (node (ref "U9") (pin "17") (pinfunction "~{WE}_17") (pintype "input"))
    )
    (net (code "184") (name "unconnected-(J2-SHIELD-PadCD2)") (class "Default")
      (node (ref "J2") (pin "CD2") (pinfunction "SHIELD_CD2") (pintype "bidirectional"))
    )
    (net (code "185") (name "unconnected-(J4-Pad2)") (class "Default")
      (node (ref "J4") (pin "2") (pinfunction "2_2") (pintype "passive"))
    )
    (net (code "186") (name "unconnected-(J4-Pad6)") (class "Default")
      (node (ref "J4") (pin "6") (pinfunction "6_6") (pintype "passive"))
    )
    (net (code "187") (name "unconnected-(J5-Pad2)") (class "Default")
      (node (ref "J5") (pin "2") (pinfunction "2_2") (pintype "passive"))
    )
    (net (code "188") (name "unconnected-(J5-Pad6)") (class "Default")
      (node (ref "J5") (pin "6") (pinfunction "6_6") (pintype "passive"))
    )
    (net (code "189") (name "unconnected-(J6-Pad4)") (class "Default")
      (node (ref "J6") (pin "4") (pinfunction "4_4") (pintype "passive"))
    )
    (net (code "190") (name "unconnected-(J6-Pad5)") (class "Default")
      (node (ref "J6") (pin "5") (pinfunction "5_5") (pintype "passive"))
    )
    (net (code "191") (name "unconnected-(J6-Pad9)") (class "Default")
      (node (ref "J6") (pin "9") (pinfunction "9_9") (pintype "passive"))
    )
    (net (code "192") (name "unconnected-(J6-Pad12)") (class "Default")
      (node (ref "J6") (pin "12") (pinfunction "12_12") (pintype "passive"))
    )
    (net (code "193") (name "unconnected-(J6-Pad15)") (class "Default")
      (node (ref "J6") (pin "15") (pinfunction "15_15") (pintype "passive"))
    )
    (net (code "194") (name "unconnected-(U4A-IO_L5N_0-PadE6)") (class "Default")
      (node (ref "U4") (pin "E6") (pinfunction "IO_L5N_0_E6") (pintype "bidirectional"))
    )
    (net (code "195") (name "unconnected-(U4A-IO_L5P_0-PadF7)") (class "Default")
      (node (ref "U4") (pin "F7") (pinfunction "IO_L5P_0_F7") (pintype "bidirectional"))
    )
    (net (code "196") (name "unconnected-(U4A-IO_L7N_0-PadC6)") (class "Default")
      (node (ref "U4") (pin "C6") (pinfunction "IO_L7N_0_C6") (pintype "bidirectional"))
    )
    (net (code "197") (name "unconnected-(U4A-IO_L36N_GCLK14_0-PadE8)") (class "Default")
      (node (ref "U4") (pin "E8") (pinfunction "IO_L36N_GCLK14_0_E8") (pintype "bidirectional"))
    )
    (net (code "198") (name "unconnected-(U4A-IO_L36P_GCLK15_0-PadE7)") (class "Default")
      (node (ref "U4") (pin "E7") (pinfunction "IO_L36P_GCLK15_0_E7") (pintype "bidirectional"))
    )
    (net (code "199") (name "unconnected-(U4A-IO_L37P_GCLK13_0-PadE10)") (class "Default")
      (node (ref "U4") (pin "E10") (pinfunction "IO_L37P_GCLK13_0_E10") (pintype "bidirectional"))
    )
    (net (code "200") (name "unconnected-(U4A-IO_L64P_SCP5_0-PadF10)") (class "Default")
      (node (ref "U4") (pin "F10") (pinfunction "IO_L64P_SCP5_0_F10") (pintype "bidirectional"))
    )
    (net (code "201") (name "unconnected-(U4A-IO_L65P_SCP3_0-PadB14)") (class "Default")
      (node (ref "U4") (pin "B14") (pinfunction "IO_L65P_SCP3_0_B14") (pintype "bidirectional"))
    )
    (net (code "202") (name "unconnected-(U4A-IO_L66N_SCP0_0-PadD12)") (class "Default")
      (node (ref "U4") (pin "D12") (pinfunction "IO_L66N_SCP0_0_D12") (pintype "bidirectional"))
    )
    (net (code "203") (name "unconnected-(U4B-IO_L30N_A20_M1A11_1-PadG11)") (class "Default")
      (node (ref "U4") (pin "G11") (pinfunction "IO_L30N_A20_M1A11_1_G11") (pintype "bidirectional"))
    )
    (net (code "204") (name "unconnected-(U4B-IO_L30P_A21_M1RESET_1-PadF12)") (class "Default")
      (node (ref "U4") (pin "F12") (pinfunction "IO_L30P_A21_M1RESET_1_F12") (pintype "bidirectional"))
    )
    (net (code "205") (name "unconnected-(U4B-IO_L38N_A4_M1CLKN_1-PadH11)") (class "Default")
      (node (ref "U4") (pin "H11") (pinfunction "IO_L38N_A4_M1CLKN_1_H11") (pintype "bidirectional"))
    )
    (net (code "206") (name "unconnected-(U4B-IO_L38P_A5_M1CLK_1-PadG12)") (class "Default")
      (node (ref "U4") (pin "G12") (pinfunction "IO_L38P_A5_M1CLK_1_G12") (pintype "bidirectional"))
    )
    (net (code "207") (name "unconnected-(U4B-IO_L39N_M1ODT_1-PadH14)") (class "Default")
      (node (ref "U4") (pin "H14") (pinfunction "IO_L39N_M1ODT_1_H14") (pintype "bidirectional"))
    )
    (net (code "208") (name "unconnected-(U4B-IO_L40N_GCLK10_M1A6_1-PadJ12)") (class "Default")
      (node (ref "U4") (pin "J12") (pinfunction "IO_L40N_GCLK10_M1A6_1_J12") (pintype "bidirectional"))
    )
    (net (code "209") (name "unconnected-(U4B-IO_L40P_GCLK11_M1A5_1-PadJ11)") (class "Default")
      (node (ref "U4") (pin "J11") (pinfunction "IO_L40P_GCLK11_M1A5_1_J11") (pintype "bidirectional"))
    )
    (net (code "210") (name "unconnected-(U4B-IO_L41P_GCLK9_IRDY1_M1RASN_1-PadJ13)") (class "Default")
      (node (ref "U4") (pin "J13") (pinfunction "IO_L41P_GCLK9_IRDY1_M1RASN_1_J13") (pintype "bidirectional"))
    )
    (net (code "211") (name "unconnected-(U4B-IO_L42N_GCLK6_TRDY1_M1LDM_1-PadK11)") (class "Default")
      (node (ref "U4") (pin "K11") (pinfunction "IO_L42N_GCLK6_TRDY1_M1LDM_1_K11") (pintype "bidirectional"))
    )
    (net (code "212") (name "unconnected-(U4B-IO_L42P_GCLK7_M1UDM_1-PadK12)") (class "Default")
      (node (ref "U4") (pin "K12") (pinfunction "IO_L42P_GCLK7_M1UDM_1_K12") (pintype "bidirectional"))
    )
    (net (code "213") (name "unconnected-(U4B-IO_L46N_FOE_B_M1DQ3_1-PadM16)") (class "Default")
      (node (ref "U4") (pin "M16") (pinfunction "IO_L46N_FOE_B_M1DQ3_1_M16") (pintype "bidirectional"))
    )
    (net (code "214") (name "unconnected-(U4B-IO_L46P_FCS_B_M1DQ2_1-PadM15)") (class "Default")
      (node (ref "U4") (pin "M15") (pinfunction "IO_L46P_FCS_B_M1DQ2_1_M15") (pintype "bidirectional"))
    )
    (net (code "215") (name "unconnected-(U4B-IO_L48N_M1DQ9_1-PadP16)") (class "Default")
      (node (ref "U4") (pin "P16") (pinfunction "IO_L48N_M1DQ9_1_P16") (pintype "bidirectional"))
    )
    (net (code "216") (name "unconnected-(U4B-IO_L48P_HDC_M1DQ8_1-PadP15)") (class "Default")
      (node (ref "U4") (pin "P15") (pinfunction "IO_L48P_HDC_M1DQ8_1_P15") (pintype "bidirectional"))
    )
    (net (code "217") (name "unconnected-(U4B-IO_L49N_M1DQ11_1-PadR16)") (class "Default")
      (node (ref "U4") (pin "R16") (pinfunction "IO_L49N_M1DQ11_1_R16") (pintype "bidirectional"))
    )
    (net (code "218") (name "unconnected-(U4B-IO_L49P_M1DQ10_1-PadR15)") (class "Default")
      (node (ref "U4") (pin "R15") (pinfunction "IO_L49P_M1DQ10_1_R15") (pintype "bidirectional"))
    )
    (net (code "219") (name "unconnected-(U4B-IO_L51N_M1DQ13_1-PadT13)") (class "Default")
      (node (ref "U4") (pin "T13") (pinfunction "IO_L51N_M1DQ13_1_T13") (pintype "bidirectional"))
    )
    (net (code "220") (name "unconnected-(U4B-IO_L51P_M1DQ12_1-PadT14)") (class "Default")
      (node (ref "U4") (pin "T14") (pinfunction "IO_L51P_M1DQ12_1_T14") (pintype "bidirectional"))
    )
    (net (code "221") (name "unconnected-(U4B-IO_L52N_M1DQ15_1-PadT12)") (class "Default")
      (node (ref "U4") (pin "T12") (pinfunction "IO_L52N_M1DQ15_1_T12") (pintype "bidirectional"))
    )
    (net (code "222") (name "unconnected-(U4B-IO_L52P_M1DQ14_1-PadR12)") (class "Default")
      (node (ref "U4") (pin "R12") (pinfunction "IO_L52P_M1DQ14_1_R12") (pintype "bidirectional"))
    )
    (net (code "223") (name "unconnected-(U4C-CMPCS_B_2-PadL11)") (class "Default")
      (node (ref "U4") (pin "L11") (pinfunction "CMPCS_B_2_L11") (pintype "bidirectional"))
    )
    (net (code "224") (name "unconnected-(U4C-IO_L2N_CMPMOSI_2-PadM11)") (class "Default")
      (node (ref "U4") (pin "M11") (pinfunction "IO_L2N_CMPMOSI_2_M11") (pintype "bidirectional"))
    )
    (net (code "225") (name "unconnected-(U4C-IO_L2P_CMPCLK_2-PadM12)") (class "Default")
      (node (ref "U4") (pin "M12") (pinfunction "IO_L2P_CMPCLK_2_M12") (pintype "bidirectional"))
    )
    (net (code "226") (name "unconnected-(U4C-IO_L13N_D10_2-PadP11)") (class "Default")
      (node (ref "U4") (pin "P11") (pinfunction "IO_L13N_D10_2_P11") (pintype "bidirectional"))
    )
    (net (code "227") (name "unconnected-(U4C-IO_L14N_D12_2-PadP9)") (class "Default")
      (node (ref "U4") (pin "P9") (pinfunction "IO_L14N_D12_2_P9") (pintype "bidirectional"))
    )
    (net (code "228") (name "unconnected-(U4C-IO_L14P_D11_2-PadN9)") (class "Default")
      (node (ref "U4") (pin "N9") (pinfunction "IO_L14P_D11_2_N9") (pintype "bidirectional"))
    )
    (net (code "229") (name "unconnected-(U4C-IO_L62N_D6_2-PadL7)") (class "Default")
      (node (ref "U4") (pin "L7") (pinfunction "IO_L62N_D6_2_L7") (pintype "bidirectional"))
    )
    (net (code "230") (name "unconnected-(U4C-IO_L62P_D5_2-PadL8)") (class "Default")
      (node (ref "U4") (pin "L8") (pinfunction "IO_L62P_D5_2_L8") (pintype "bidirectional"))
    )
    (net (code "231") (name "unconnected-(U4D-IO_L1N_VREF_3-PadM3)") (class "Default")
      (node (ref "U4") (pin "M3") (pinfunction "IO_L1N_VREF_3_M3") (pintype "bidirectional"))
    )
    (net (code "232") (name "unconnected-(U4D-IO_L1P_3-PadM4)") (class "Default")
      (node (ref "U4") (pin "M4") (pinfunction "IO_L1P_3_M4") (pintype "bidirectional"))
    )
    (net (code "233") (name "unconnected-(U4D-IO_L2N_3-PadN4)") (class "Default")
      (node (ref "U4") (pin "N4") (pinfunction "IO_L2N_3_N4") (pintype "bidirectional"))
    )
    (net (code "234") (name "unconnected-(U4D-IO_L2P_3-PadM5)") (class "Default")
      (node (ref "U4") (pin "M5") (pinfunction "IO_L2P_3_M5") (pintype "bidirectional"))
    )
    (net (code "235") (name "unconnected-(U4D-IO_L42P_GCLK25_TRDY2_M3UDM_3-PadK3)") (class "Default")
      (node (ref "U4") (pin "K3") (pinfunction "IO_L42P_GCLK25_TRDY2_M3UDM_3_K3") (pintype "bidirectional"))
    )
    (net (code "236") (name "unconnected-(U4D-IO_L43N_GCLK22_IRDY2_M3CASN_3-PadH5)") (class "Default")
      (node (ref "U4") (pin "H5") (pinfunction "IO_L43N_GCLK22_IRDY2_M3CASN_3_H5") (pintype "bidirectional"))
    )
    (net (code "237") (name "unconnected-(U4D-IO_L43P_GCLK23_M3RASN_3-PadJ6)") (class "Default")
      (node (ref "U4") (pin "J6") (pinfunction "IO_L43P_GCLK23_M3RASN_3_J6") (pintype "bidirectional"))
    )
    (net (code "238") (name "unconnected-(U4D-IO_L47N_M3A1_3-PadK6)") (class "Default")
      (node (ref "U4") (pin "K6") (pinfunction "IO_L47N_M3A1_3_K6") (pintype "bidirectional"))
    )
    (net (code "239") (name "unconnected-(U4D-IO_L47P_M3A0_3-PadK5)") (class "Default")
      (node (ref "U4") (pin "K5") (pinfunction "IO_L47P_M3A0_3_K5") (pintype "bidirectional"))
    )
    (net (code "240") (name "unconnected-(U4D-IO_L51N_M3A4_3-PadG5)") (class "Default")
      (node (ref "U4") (pin "G5") (pinfunction "IO_L51N_M3A4_3_G5") (pintype "bidirectional"))
    )
    (net (code "241") (name "unconnected-(U4D-IO_L51P_M3A10_3-PadG6)") (class "Default")
      (node (ref "U4") (pin "G6") (pinfunction "IO_L51P_M3A10_3_G6") (pintype "bidirectional"))
    )
    (net (code "242") (name "unconnected-(U4D-IO_L55N_M3A14_3-PadF5)") (class "Default")
      (node (ref "U4") (pin "F5") (pinfunction "IO_L55N_M3A14_3_F5") (pintype "bidirectional"))
    )
    (net (code "243") (name "unconnected-(U4D-IO_L55P_M3A13_3-PadF6)") (class "Default")
      (node (ref "U4") (pin "F6") (pinfunction "IO_L55P_M3A13_3_F6") (pintype "bidirectional"))
    )
    (net (code "244") (name "unconnected-(U4F-SUSPEND-PadP14)") (class "Default")
      (node (ref "U4") (pin "P14") (pinfunction "SUSPEND_P14") (pintype "input"))
    )
    (net (code "245") (name "unconnected-(U7-ACBUS0{slash}TXDEN{slash}GPIOH0-Pad26)") (class "Default")
      (node (ref "U7") (pin "26") (pinfunction "ACBUS0/TXDEN/GPIOH0_26") (pintype "bidirectional"))
    )
    (net (code "246") (name "unconnected-(U7-ACBUS1{slash}GPIOH1-Pad27)") (class "Default")
      (node (ref "U7") (pin "27") (pinfunction "ACBUS1/GPIOH1_27") (pintype "bidirectional"))
    )
    (net (code "247") (name "unconnected-(U7-ACBUS2{slash}GPIOH2-Pad28)") (class "Default")
      (node (ref "U7") (pin "28") (pinfunction "ACBUS2/GPIOH2_28") (pintype "bidirectional"))
    )
    (net (code "248") (name "unconnected-(U7-ACBUS3{slash}RXLED#{slash}GPIOH3-Pad29)") (class "Default")
      (node (ref "U7") (pin "29") (pinfunction "ACBUS3/RXLED#/GPIOH3_29") (pintype "bidirectional"))
    )
    (net (code "249") (name "unconnected-(U7-ACBUS4{slash}TXLED#{slash}GPIOH4-Pad30)") (class "Default")
      (node (ref "U7") (pin "30") (pinfunction "ACBUS4/TXLED#/GPIOH4_30") (pintype "bidirectional"))
    )
    (net (code "250") (name "unconnected-(U7-ACBUS5{slash}GPIOH5-Pad32)") (class "Default")
      (node (ref "U7") (pin "32") (pinfunction "ACBUS5/GPIOH5_32") (pintype "bidirectional"))
    )
    (net (code "251") (name "unconnected-(U7-ACBUS6{slash}GPIOH6-Pad33)") (class "Default")
      (node (ref "U7") (pin "33") (pinfunction "ACBUS6/GPIOH6_33") (pintype "bidirectional"))
    )
    (net (code "252") (name "unconnected-(U7-ACBUS7{slash}GPIOH7-Pad34)") (class "Default")
      (node (ref "U7") (pin "34") (pinfunction "ACBUS7/GPIOH7_34") (pintype "bidirectional"))
    )
    (net (code "253") (name "unconnected-(U7-ADBUS4{slash}DTR#{slash}GPIOL0-Pad21)") (class "Default")
      (node (ref "U7") (pin "21") (pinfunction "ADBUS4/DTR#/GPIOL0_21") (pintype "bidirectional"))
    )
    (net (code "254") (name "unconnected-(U7-ADBUS5{slash}DSR#{slash}GPIOL1-Pad22)") (class "Default")
      (node (ref "U7") (pin "22") (pinfunction "ADBUS5/DSR#/GPIOL1_22") (pintype "bidirectional"))
    )
    (net (code "255") (name "unconnected-(U7-ADBUS6{slash}DCD#{slash}GPIOL2-Pad23)") (class "Default")
      (node (ref "U7") (pin "23") (pinfunction "ADBUS6/DCD#/GPIOL2_23") (pintype "bidirectional"))
    )
    (net (code "256") (name "unconnected-(U7-ADBUS7{slash}RI#{slash}GPIOL3-Pad24)") (class "Default")
      (node (ref "U7") (pin "24") (pinfunction "ADBUS7/RI#/GPIOL3_24") (pintype "bidirectional"))
    )
    (net (code "257") (name "unconnected-(U7-BCBUS0{slash}GPIOH1-Pad48)") (class "Default")
      (node (ref "U7") (pin "48") (pinfunction "BCBUS0/GPIOH1_48") (pintype "bidirectional"))
    )
    (net (code "258") (name "unconnected-(U7-BCBUS1{slash}GPIOH2-Pad52)") (class "Default")
      (node (ref "U7") (pin "52") (pinfunction "BCBUS1/GPIOH2_52") (pintype "bidirectional"))
    )
    (net (code "259") (name "unconnected-(U7-BCBUS2-Pad53)") (class "Default")
      (node (ref "U7") (pin "53") (pinfunction "BCBUS2_53") (pintype "bidirectional"))
    )
    (net (code "260") (name "unconnected-(U7-BCBUS3{slash}RXLED#{slash}GPIOH3-Pad54)") (class "Default")
      (node (ref "U7") (pin "54") (pinfunction "BCBUS3/RXLED#/GPIOH3_54") (pintype "bidirectional"))
    )
    (net (code "261") (name "unconnected-(U7-BCBUS4{slash}TXLED#{slash}GPIOH4-Pad55)") (class "Default")
      (node (ref "U7") (pin "55") (pinfunction "BCBUS4/TXLED#/GPIOH4_55") (pintype "bidirectional"))
    )
    (net (code "262") (name "unconnected-(U7-BCBUS5{slash}GPIOH5-Pad57)") (class "Default")
      (node (ref "U7") (pin "57") (pinfunction "BCBUS5/GPIOH5_57") (pintype "bidirectional"))
    )
    (net (code "263") (name "unconnected-(U7-BCBUS6{slash}GPIOH6-Pad58)") (class "Default")
      (node (ref "U7") (pin "58") (pinfunction "BCBUS6/GPIOH6_58") (pintype "bidirectional"))
    )
    (net (code "264") (name "unconnected-(U7-BCBUS7{slash}GPIOH7-Pad59)") (class "Default")
      (node (ref "U7") (pin "59") (pinfunction "BCBUS7/GPIOH7_59") (pintype "bidirectional"))
    )
    (net (code "265") (name "unconnected-(U7-BDBUS4{slash}DTR#{slash}GPIOL0-Pad43)") (class "Default")
      (node (ref "U7") (pin "43") (pinfunction "BDBUS4/DTR#/GPIOL0_43") (pintype "bidirectional"))
    )
    (net (code "266") (name "unconnected-(U7-BDBUS5{slash}DSR#{slash}GPIOL1-Pad44)") (class "Default")
      (node (ref "U7") (pin "44") (pinfunction "BDBUS5/DSR#/GPIOL1_44") (pintype "bidirectional"))
    )
    (net (code "267") (name "unconnected-(U7-BDBUS6{slash}DCD#{slash}GPIOL2-Pad45)") (class "Default")
      (node (ref "U7") (pin "45") (pinfunction "BDBUS6/DCD#/GPIOL2_45") (pintype "bidirectional"))
    )
    (net (code "268") (name "unconnected-(U7-BDBUS7{slash}RI#{slash}GPIOL3-Pad46)") (class "Default")
      (node (ref "U7") (pin "46") (pinfunction "BDBUS7/RI#/GPIOL3_46") (pintype "bidirectional"))
    )
    (net (code "269") (name "unconnected-(U7-PWREN#-Pad60)") (class "Default")
      (node (ref "U7") (pin "60") (pinfunction "PWREN#_60") (pintype "bidirectional"))
    )
    (net (code "270") (name "unconnected-(U7-SUSPEND#-Pad36)") (class "Default")
      (node (ref "U7") (pin "36") (pinfunction "SUSPEND#_36") (pintype "bidirectional"))
    )
  )
)
